# FPGA2.net
KiCad netlist of a schematic drawn in Altium Designer
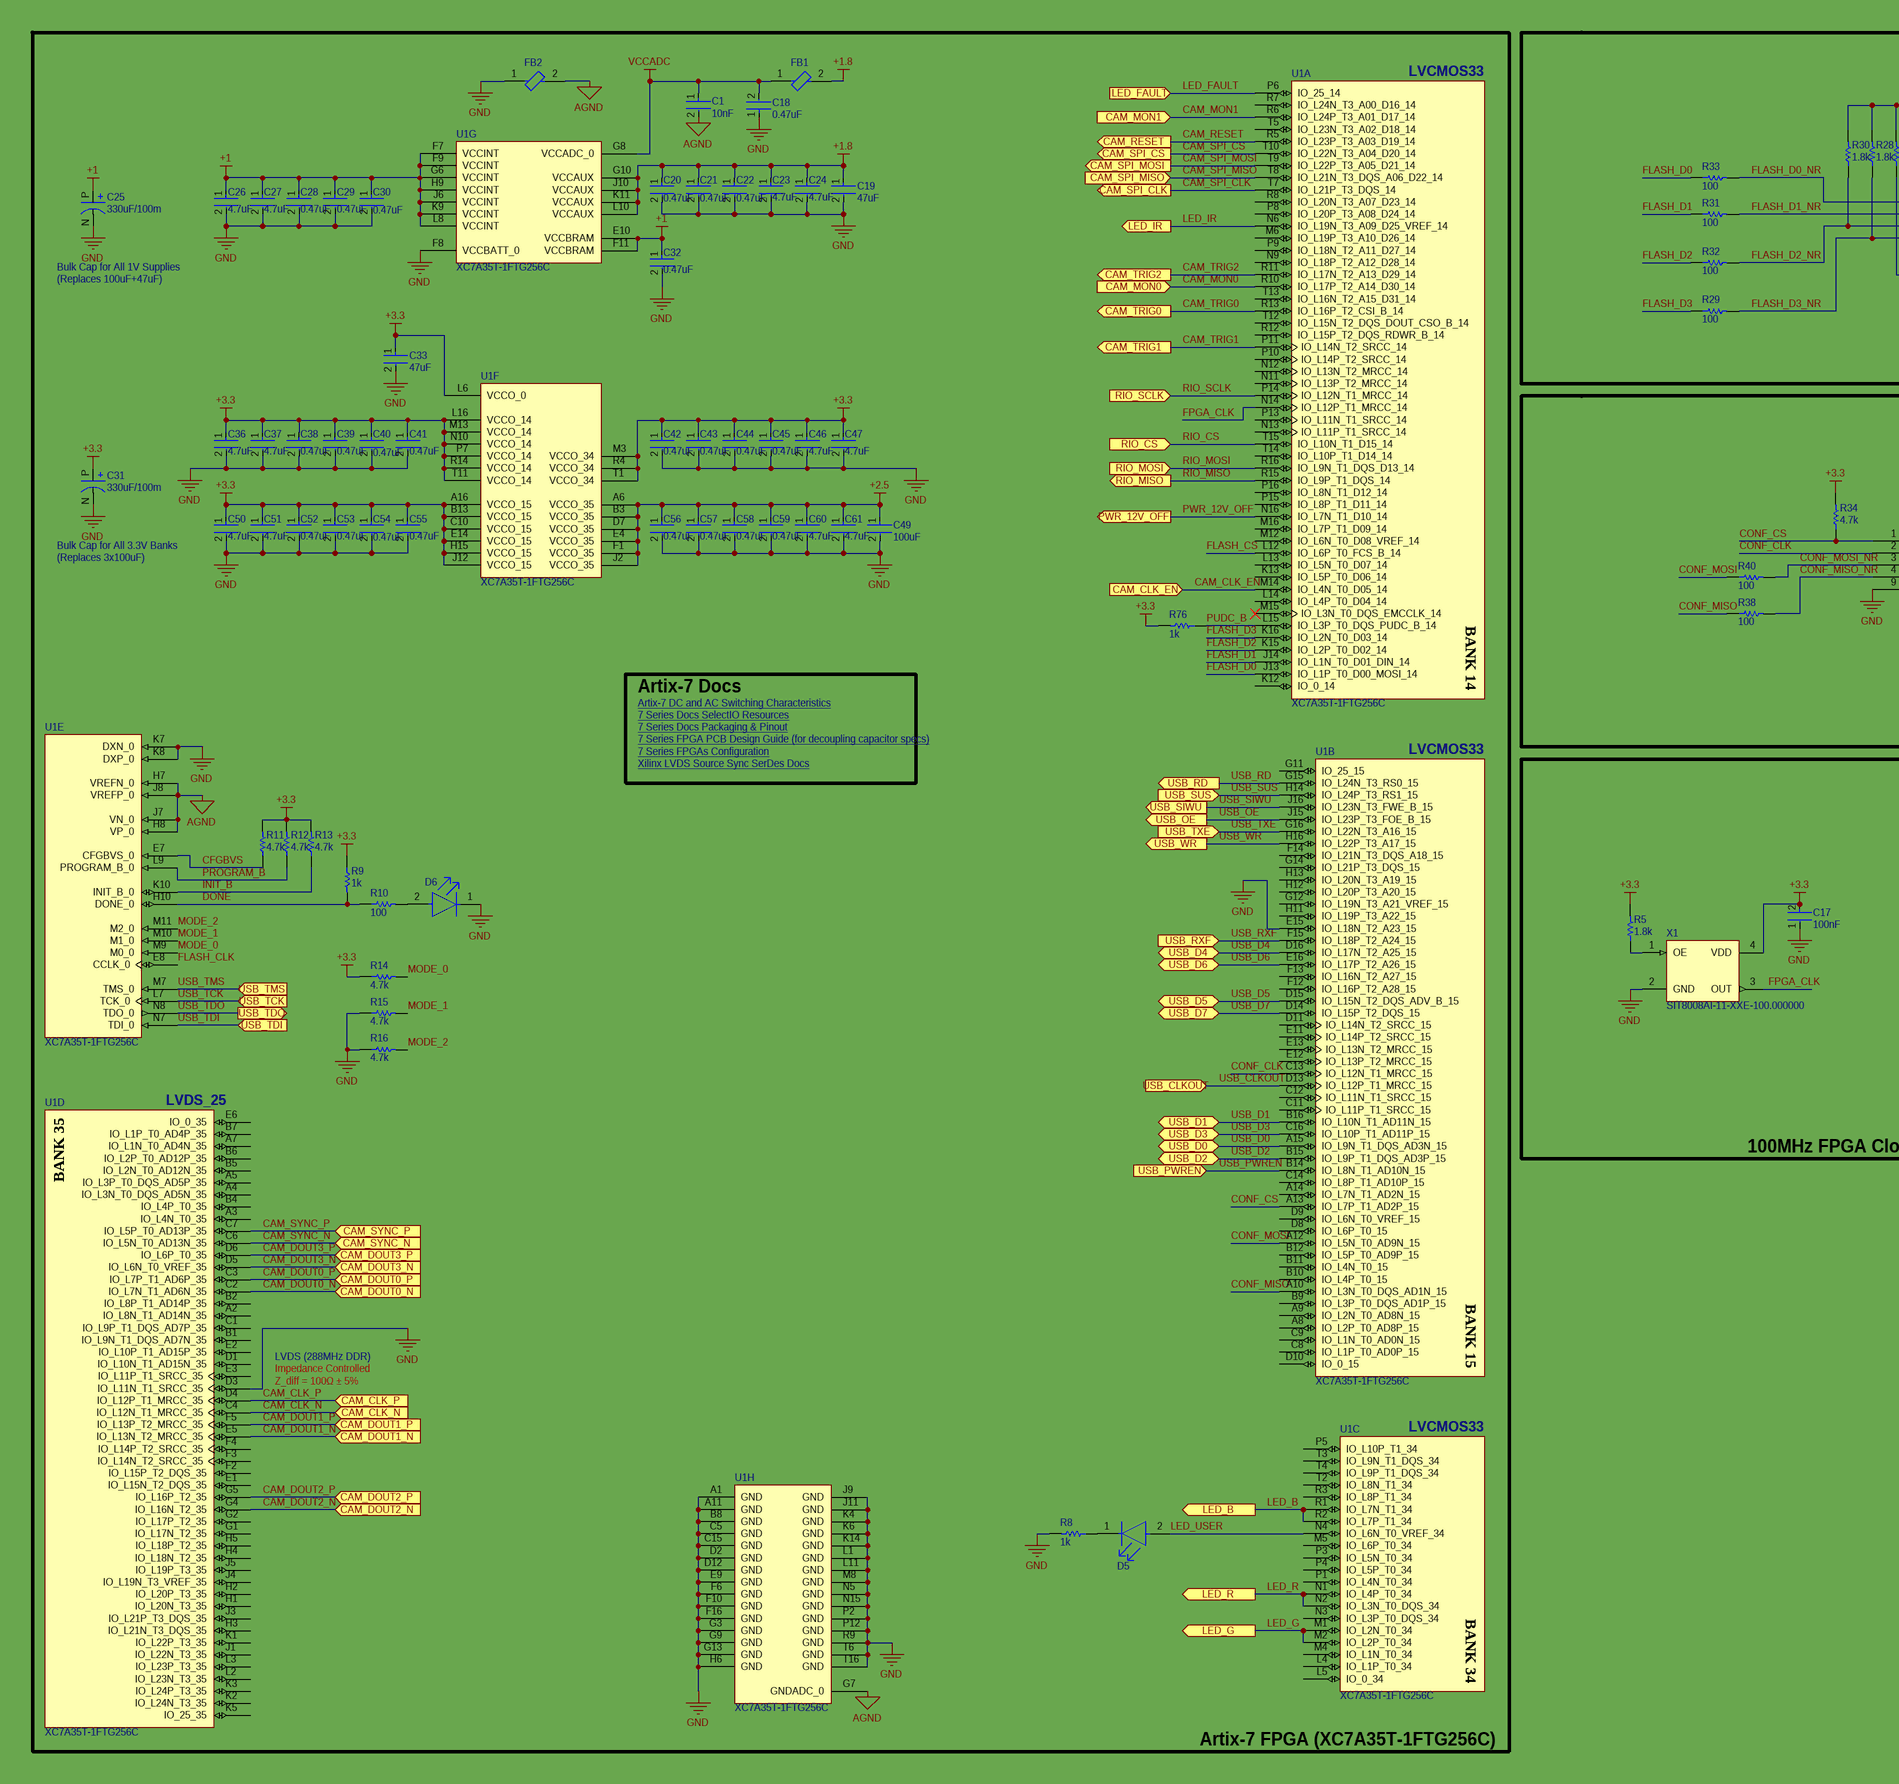
[diagram p0: FPGA2.SchDoc, left]
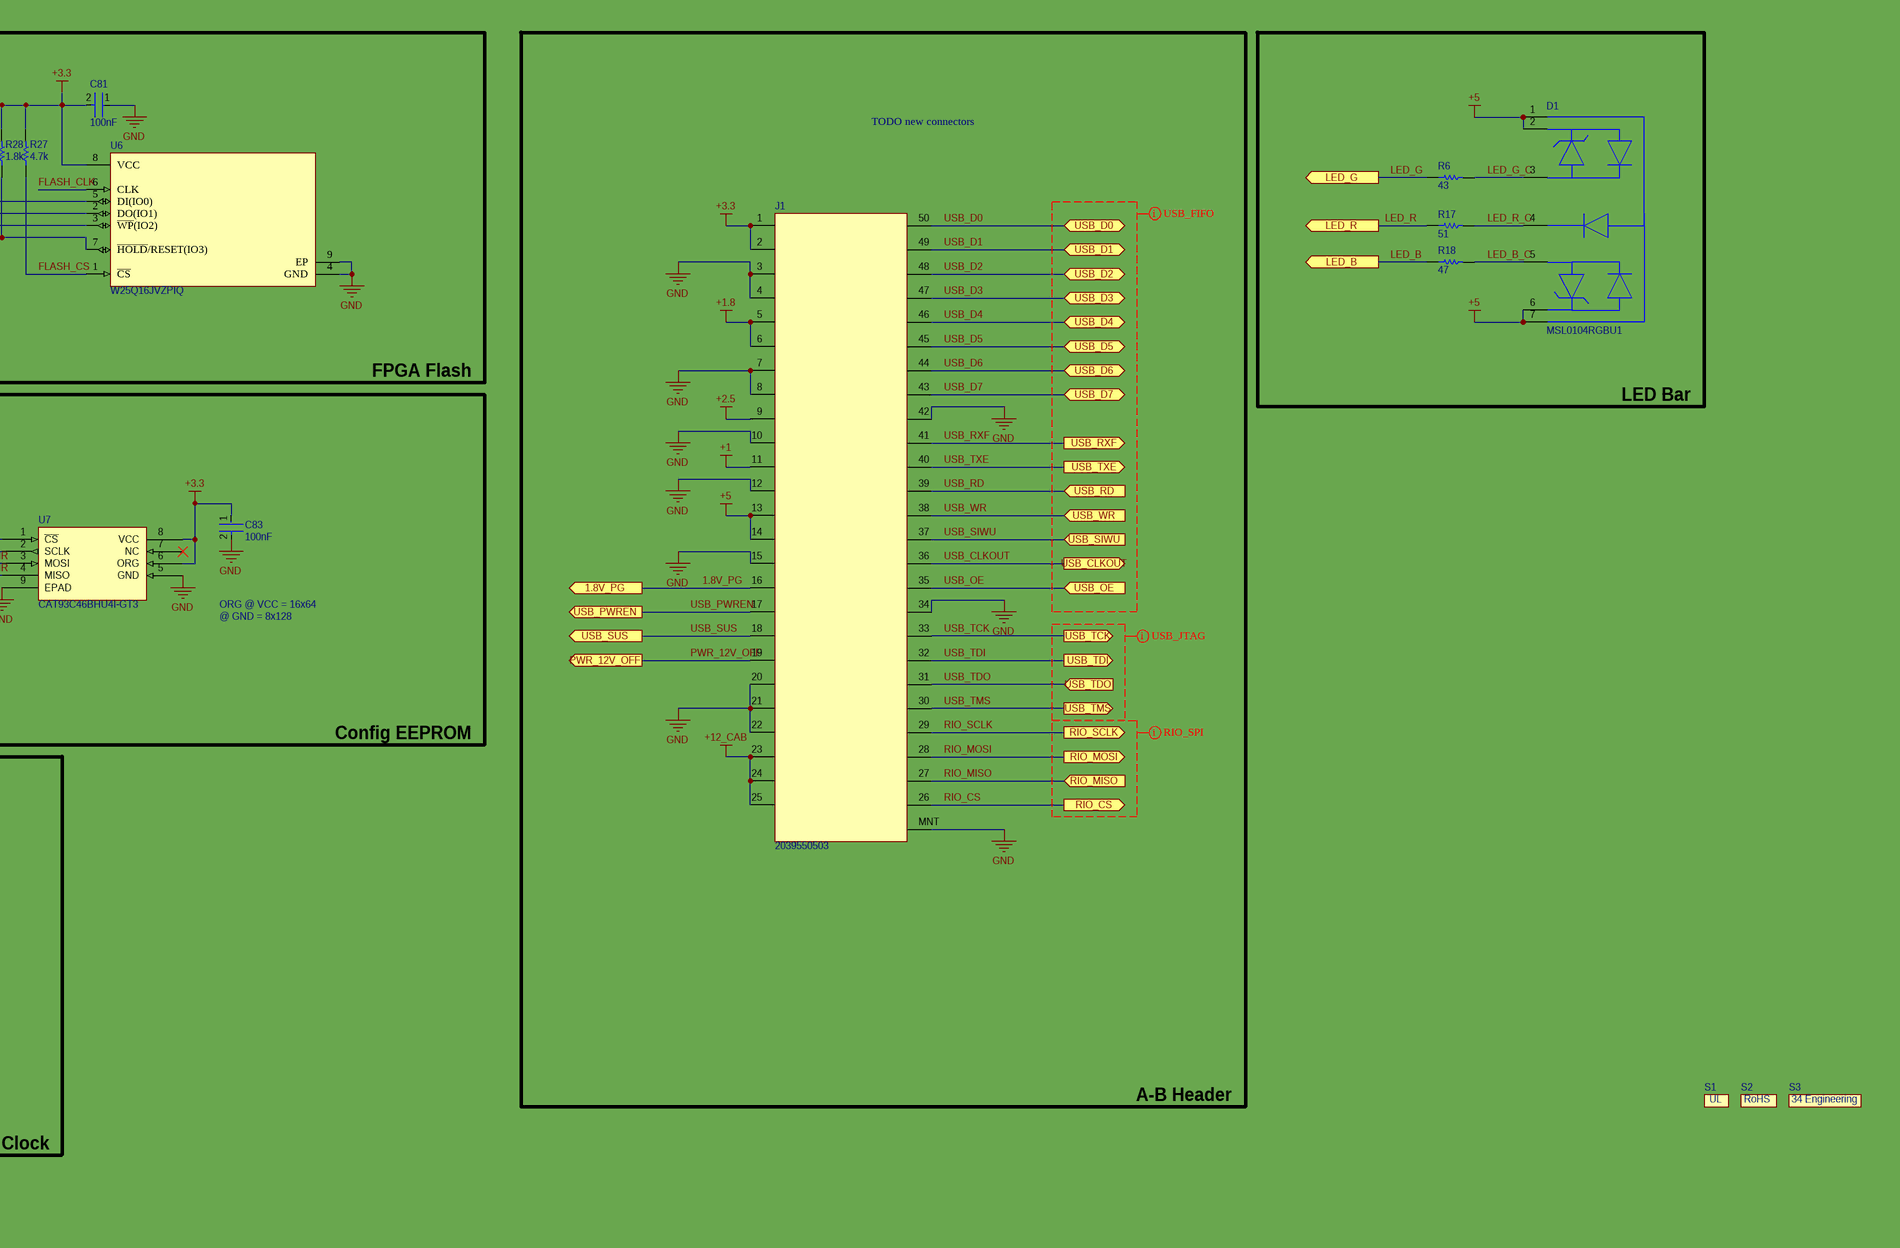
[diagram p1: FPGA2.SchDoc, right]

(export (version "E")
  (design (tool "Eeschema 10.0.6"))
  (components
    (comp (ref "C1")
      (value "10nF")
      (footprint "FP-GRM033-0_03-IPC_C")
      (description "Chip Multilayer Ceramic Capacitors for General Purpose, 0201, 10000pF, X7R, 15%, 10%, 10V")
      (fields (field (name "VOLTAGE") "10V") (field (name "TOLERANCE") "10%"))
      (libsource (lib "Altium Content Vault") (part "b4654b650e69147ec39a6b967a45e02"))
    )
    (comp (ref "C17")
      (value "100nF")
      (footprint "FP-GRM15-IPC_C")
      (description "CAP CER 0.1UF 16V X7R 0402")
      (fields (field (name "MANUFACTURER PART NUMBER") "GRM155R71C104KA88D") (field (name "TOLERANCE") "10%"))
      (libsource (lib "Altium Content Vault") (part "236180d848d6139a670b325ea6854c9"))
    )
    (comp (ref "C18")
      (value "0.47uF")
      (footprint "FP-GRM033-0_03-IPC_C")
      (description "Chip Multilayer Ceramic Capacitors for General Purpose, 0201, 0.47uF, X5R, 15%, 10%, 6.3V")
      (fields (field (name "TOLERANCE") "10%"))
      (libsource (lib "Altium Content Vault") (part "b4654b650e69147ec39a6b967a45e02"))
    )
    (comp (ref "C19")
      (value "47uF")
      (footprint "FP-GRM188-0_2-MFG")
      (description "Chip Multilayer Ceramic Capacitors for General Purpose, 0603, 47uF, X5R, 15%, 20%, 6.3V")
      (fields (field (name "TOLERANCE") "20%"))
      (libsource (lib "Altium Content Vault") (part "11868f565c42a9108669ba33697ecf6"))
    )
    (comp (ref "C20")
      (value "0.47uF")
      (footprint "FP-GRM033-0_03-IPC_C")
      (description "Chip Multilayer Ceramic Capacitors for General Purpose, 0201, 0.47uF, X5R, 15%, 10%, 6.3V")
      (fields (field (name "TOLERANCE") "10%"))
      (libsource (lib "Altium Content Vault") (part "b4654b650e69147ec39a6b967a45e02"))
    )
    (comp (ref "C21")
      (value "0.47uF")
      (footprint "FP-GRM033-0_03-IPC_C")
      (description "Chip Multilayer Ceramic Capacitors for General Purpose, 0201, 0.47uF, X5R, 15%, 10%, 6.3V")
      (fields (field (name "TOLERANCE") "10%"))
      (libsource (lib "Altium Content Vault") (part "b4654b650e69147ec39a6b967a45e02"))
    )
    (comp (ref "C22")
      (value "0.47uF")
      (footprint "FP-GRM033-0_03-IPC_C")
      (description "Chip Multilayer Ceramic Capacitors for General Purpose, 0201, 0.47uF, X5R, 15%, 10%, 6.3V")
      (fields (field (name "TOLERANCE") "10%"))
      (libsource (lib "Altium Content Vault") (part "b4654b650e69147ec39a6b967a45e02"))
    )
    (comp (ref "C23")
      (value "4.7uF")
      (footprint "FP-GRM155-0_1-IPC_B")
      (description "Chip Multilayer Ceramic Capacitors for General Purpose, 0402, 4.7uF, X5R, 15%, 20%, 6.3V")
      (fields (field (name "VOLTAGE") "6.3V") (field (name "TOLERANCE") "20%"))
      (libsource (lib "Altium Content Vault") (part "11868f565c42a9108669ba33697ecf6"))
    )
    (comp (ref "C24")
      (value "4.7uF")
      (footprint "FP-GRM155-0_1-IPC_B")
      (description "Chip Multilayer Ceramic Capacitors for General Purpose, 0402, 4.7uF, X5R, 15%, 20%, 6.3V")
      (fields (field (name "VOLTAGE") "6.3V") (field (name "TOLERANCE") "20%"))
      (libsource (lib "Altium Content Vault") (part "11868f565c42a9108669ba33697ecf6"))
    )
    (comp (ref "C25")
      (value "330uF/100m")
      (footprint "NOSD337M004R0100")
      (description "330uF +/-20% 4 V dc SMD Niobium Capacitor; 7343-31 package; ESR 0.1Ohms NOS")
      (fields
        (field (name "MANUFACTURER") "Kyocera AVX")
        (field (name "MANUFACTURER PART NUMBER") "NOSD337M004R0100")
      )
      (libsource (lib "Virtex") (part "NOSD337M004R0100"))
    )
    (comp (ref "C26")
      (value "4.7uF")
      (footprint "FP-GRM155-0_1-IPC_B")
      (description "Chip Multilayer Ceramic Capacitors for General Purpose, 0402, 4.7uF, X5R, 15%, 20%, 6.3V")
      (fields (field (name "VOLTAGE") "6.3V") (field (name "TOLERANCE") "20%"))
      (libsource (lib "Altium Content Vault") (part "11868f565c42a9108669ba33697ecf6"))
    )
    (comp (ref "C27")
      (value "4.7uF")
      (footprint "FP-GRM155-0_1-IPC_B")
      (description "Chip Multilayer Ceramic Capacitors for General Purpose, 0402, 4.7uF, X5R, 15%, 20%, 6.3V")
      (fields (field (name "VOLTAGE") "6.3V") (field (name "TOLERANCE") "20%"))
      (libsource (lib "Altium Content Vault") (part "11868f565c42a9108669ba33697ecf6"))
    )
    (comp (ref "C28")
      (value "0.47uF")
      (footprint "FP-GRM033-0_03-IPC_C")
      (description "Chip Multilayer Ceramic Capacitors for General Purpose, 0201, 0.47uF, X5R, 15%, 10%, 6.3V")
      (fields (field (name "TOLERANCE") "10%"))
      (libsource (lib "Altium Content Vault") (part "b4654b650e69147ec39a6b967a45e02"))
    )
    (comp (ref "C29")
      (value "0.47uF")
      (footprint "FP-GRM033-0_03-IPC_C")
      (description "Chip Multilayer Ceramic Capacitors for General Purpose, 0201, 0.47uF, X5R, 15%, 10%, 6.3V")
      (fields (field (name "TOLERANCE") "10%"))
      (libsource (lib "Altium Content Vault") (part "b4654b650e69147ec39a6b967a45e02"))
    )
    (comp (ref "C30")
      (value "0.47uF")
      (footprint "FP-GRM033-0_03-IPC_C")
      (description "Chip Multilayer Ceramic Capacitors for General Purpose, 0201, 0.47uF, X5R, 15%, 10%, 6.3V")
      (fields (field (name "TOLERANCE") "10%"))
      (libsource (lib "Altium Content Vault") (part "b4654b650e69147ec39a6b967a45e02"))
    )
    (comp (ref "C31")
      (value "330uF/100m")
      (footprint "NOSD337M004R0100")
      (description "330uF +/-20% 4 V dc SMD Niobium Capacitor; 7343-31 package; ESR 0.1Ohms NOS")
      (fields
        (field (name "MANUFACTURER") "Kyocera AVX")
        (field (name "MANUFACTURER PART NUMBER") "NOSD337M004R0100")
      )
      (libsource (lib "Virtex") (part "NOSD337M004R0100"))
    )
    (comp (ref "C32")
      (value "0.47uF")
      (footprint "FP-GRM033-0_03-IPC_C")
      (description "Chip Multilayer Ceramic Capacitors for General Purpose, 0201, 0.47uF, X5R, 15%, 10%, 6.3V")
      (fields (field (name "TOLERANCE") "10%"))
      (libsource (lib "Altium Content Vault") (part "b4654b650e69147ec39a6b967a45e02"))
    )
    (comp (ref "C33")
      (value "47uF")
      (footprint "FP-GRM188-0_2-MFG")
      (description "Chip Multilayer Ceramic Capacitors for General Purpose, 0603, 47uF, X5R, 15%, 20%, 6.3V")
      (fields (field (name "TOLERANCE") "20%"))
      (libsource (lib "Altium Content Vault") (part "11868f565c42a9108669ba33697ecf6"))
    )
    (comp (ref "C36")
      (value "4.7uF")
      (footprint "FP-GRM155-0_1-IPC_B")
      (description "Chip Multilayer Ceramic Capacitors for General Purpose, 0402, 4.7uF, X5R, 15%, 20%, 6.3V")
      (fields (field (name "VOLTAGE") "6.3V") (field (name "TOLERANCE") "20%"))
      (libsource (lib "Altium Content Vault") (part "11868f565c42a9108669ba33697ecf6"))
    )
    (comp (ref "C37")
      (value "4.7uF")
      (footprint "FP-GRM155-0_1-IPC_B")
      (description "Chip Multilayer Ceramic Capacitors for General Purpose, 0402, 4.7uF, X5R, 15%, 20%, 6.3V")
      (fields (field (name "VOLTAGE") "6.3V") (field (name "TOLERANCE") "20%"))
      (libsource (lib "Altium Content Vault") (part "11868f565c42a9108669ba33697ecf6"))
    )
    (comp (ref "C38")
      (value "0.47uF")
      (footprint "FP-GRM033-0_03-IPC_C")
      (description "Chip Multilayer Ceramic Capacitors for General Purpose, 0201, 0.47uF, X5R, 15%, 10%, 6.3V")
      (fields (field (name "TOLERANCE") "10%"))
      (libsource (lib "Altium Content Vault") (part "b4654b650e69147ec39a6b967a45e02"))
    )
    (comp (ref "C39")
      (value "0.47uF")
      (footprint "FP-GRM033-0_03-IPC_C")
      (description "Chip Multilayer Ceramic Capacitors for General Purpose, 0201, 0.47uF, X5R, 15%, 10%, 6.3V")
      (fields (field (name "TOLERANCE") "10%"))
      (libsource (lib "Altium Content Vault") (part "b4654b650e69147ec39a6b967a45e02"))
    )
    (comp (ref "C40")
      (value "0.47uF")
      (footprint "FP-GRM033-0_03-IPC_C")
      (description "Chip Multilayer Ceramic Capacitors for General Purpose, 0201, 0.47uF, X5R, 15%, 10%, 6.3V")
      (fields (field (name "TOLERANCE") "10%"))
      (libsource (lib "Altium Content Vault") (part "b4654b650e69147ec39a6b967a45e02"))
    )
    (comp (ref "C41")
      (value "0.47uF")
      (footprint "FP-GRM033-0_03-IPC_C")
      (description "Chip Multilayer Ceramic Capacitors for General Purpose, 0201, 0.47uF, X5R, 15%, 10%, 6.3V")
      (fields (field (name "TOLERANCE") "10%"))
      (libsource (lib "Altium Content Vault") (part "b4654b650e69147ec39a6b967a45e02"))
    )
    (comp (ref "C42")
      (value "0.47uF")
      (footprint "FP-GRM033-0_03-IPC_C")
      (description "Chip Multilayer Ceramic Capacitors for General Purpose, 0201, 0.47uF, X5R, 15%, 10%, 6.3V")
      (fields (field (name "TOLERANCE") "10%"))
      (libsource (lib "Altium Content Vault") (part "b4654b650e69147ec39a6b967a45e02"))
    )
    (comp (ref "C43")
      (value "0.47uF")
      (footprint "FP-GRM033-0_03-IPC_C")
      (description "Chip Multilayer Ceramic Capacitors for General Purpose, 0201, 0.47uF, X5R, 15%, 10%, 6.3V")
      (fields (field (name "TOLERANCE") "10%"))
      (libsource (lib "Altium Content Vault") (part "b4654b650e69147ec39a6b967a45e02"))
    )
    (comp (ref "C44")
      (value "0.47uF")
      (footprint "FP-GRM033-0_03-IPC_C")
      (description "Chip Multilayer Ceramic Capacitors for General Purpose, 0201, 0.47uF, X5R, 15%, 10%, 6.3V")
      (fields (field (name "TOLERANCE") "10%"))
      (libsource (lib "Altium Content Vault") (part "b4654b650e69147ec39a6b967a45e02"))
    )
    (comp (ref "C45")
      (value "0.47uF")
      (footprint "FP-GRM033-0_03-IPC_C")
      (description "Chip Multilayer Ceramic Capacitors for General Purpose, 0201, 0.47uF, X5R, 15%, 10%, 6.3V")
      (fields (field (name "TOLERANCE") "10%"))
      (libsource (lib "Altium Content Vault") (part "b4654b650e69147ec39a6b967a45e02"))
    )
    (comp (ref "C46")
      (value "4.7uF")
      (footprint "FP-GRM155-0_1-IPC_B")
      (description "Chip Multilayer Ceramic Capacitors for General Purpose, 0402, 4.7uF, X5R, 15%, 20%, 6.3V")
      (fields (field (name "VOLTAGE") "6.3V") (field (name "TOLERANCE") "20%"))
      (libsource (lib "Altium Content Vault") (part "11868f565c42a9108669ba33697ecf6"))
    )
    (comp (ref "C47")
      (value "4.7uF")
      (footprint "FP-GRM155-0_1-IPC_B")
      (description "Chip Multilayer Ceramic Capacitors for General Purpose, 0402, 4.7uF, X5R, 15%, 20%, 6.3V")
      (fields (field (name "VOLTAGE") "6.3V") (field (name "TOLERANCE") "20%"))
      (libsource (lib "Altium Content Vault") (part "11868f565c42a9108669ba33697ecf6"))
    )
    (comp (ref "C49")
      (value "100uF")
      (footprint "FP-GRM21B-0_2-e0_2_0_7-MFG")
      (description "Chip Multilayer Ceramic Capacitors for General Purpose, 0805, 100uF, X5R, 15%, 20%, 6.3V")
      (fields (field (name "TOLERANCE") "20%"))
      (libsource (lib "Altium Content Vault") (part "b4654b650e69147ec39a6b967a45e02"))
    )
    (comp (ref "C50")
      (value "4.7uF")
      (footprint "FP-GRM155-0_1-IPC_B")
      (description "Chip Multilayer Ceramic Capacitors for General Purpose, 0402, 4.7uF, X5R, 15%, 20%, 6.3V")
      (fields (field (name "VOLTAGE") "6.3V") (field (name "TOLERANCE") "20%"))
      (libsource (lib "Altium Content Vault") (part "11868f565c42a9108669ba33697ecf6"))
    )
    (comp (ref "C51")
      (value "4.7uF")
      (footprint "FP-GRM155-0_1-IPC_B")
      (description "Chip Multilayer Ceramic Capacitors for General Purpose, 0402, 4.7uF, X5R, 15%, 20%, 6.3V")
      (fields (field (name "VOLTAGE") "6.3V") (field (name "TOLERANCE") "20%"))
      (libsource (lib "Altium Content Vault") (part "11868f565c42a9108669ba33697ecf6"))
    )
    (comp (ref "C52")
      (value "0.47uF")
      (footprint "FP-GRM033-0_03-IPC_C")
      (description "Chip Multilayer Ceramic Capacitors for General Purpose, 0201, 0.47uF, X5R, 15%, 10%, 6.3V")
      (fields (field (name "TOLERANCE") "10%"))
      (libsource (lib "Altium Content Vault") (part "b4654b650e69147ec39a6b967a45e02"))
    )
    (comp (ref "C53")
      (value "0.47uF")
      (footprint "FP-GRM033-0_03-IPC_C")
      (description "Chip Multilayer Ceramic Capacitors for General Purpose, 0201, 0.47uF, X5R, 15%, 10%, 6.3V")
      (fields (field (name "TOLERANCE") "10%"))
      (libsource (lib "Altium Content Vault") (part "b4654b650e69147ec39a6b967a45e02"))
    )
    (comp (ref "C54")
      (value "0.47uF")
      (footprint "FP-GRM033-0_03-IPC_C")
      (description "Chip Multilayer Ceramic Capacitors for General Purpose, 0201, 0.47uF, X5R, 15%, 10%, 6.3V")
      (fields (field (name "TOLERANCE") "10%"))
      (libsource (lib "Altium Content Vault") (part "b4654b650e69147ec39a6b967a45e02"))
    )
    (comp (ref "C55")
      (value "0.47uF")
      (footprint "FP-GRM033-0_03-IPC_C")
      (description "Chip Multilayer Ceramic Capacitors for General Purpose, 0201, 0.47uF, X5R, 15%, 10%, 6.3V")
      (fields (field (name "TOLERANCE") "10%"))
      (libsource (lib "Altium Content Vault") (part "b4654b650e69147ec39a6b967a45e02"))
    )
    (comp (ref "C56")
      (value "0.47uF")
      (footprint "FP-GRM033-0_03-IPC_C")
      (description "Chip Multilayer Ceramic Capacitors for General Purpose, 0201, 0.47uF, X5R, 15%, 10%, 6.3V")
      (fields (field (name "TOLERANCE") "10%"))
      (libsource (lib "Altium Content Vault") (part "b4654b650e69147ec39a6b967a45e02"))
    )
    (comp (ref "C57")
      (value "0.47uF")
      (footprint "FP-GRM033-0_03-IPC_C")
      (description "Chip Multilayer Ceramic Capacitors for General Purpose, 0201, 0.47uF, X5R, 15%, 10%, 6.3V")
      (fields (field (name "TOLERANCE") "10%"))
      (libsource (lib "Altium Content Vault") (part "b4654b650e69147ec39a6b967a45e02"))
    )
    (comp (ref "C58")
      (value "0.47uF")
      (footprint "FP-GRM033-0_03-IPC_C")
      (description "Chip Multilayer Ceramic Capacitors for General Purpose, 0201, 0.47uF, X5R, 15%, 10%, 6.3V")
      (fields (field (name "TOLERANCE") "10%"))
      (libsource (lib "Altium Content Vault") (part "b4654b650e69147ec39a6b967a45e02"))
    )
    (comp (ref "C59")
      (value "0.47uF")
      (footprint "FP-GRM033-0_03-IPC_C")
      (description "Chip Multilayer Ceramic Capacitors for General Purpose, 0201, 0.47uF, X5R, 15%, 10%, 6.3V")
      (fields (field (name "TOLERANCE") "10%"))
      (libsource (lib "Altium Content Vault") (part "b4654b650e69147ec39a6b967a45e02"))
    )
    (comp (ref "C60")
      (value "4.7uF")
      (footprint "FP-GRM155-0_1-IPC_B")
      (description "Chip Multilayer Ceramic Capacitors for General Purpose, 0402, 4.7uF, X5R, 15%, 20%, 6.3V")
      (fields (field (name "VOLTAGE") "6.3V") (field (name "TOLERANCE") "20%"))
      (libsource (lib "Altium Content Vault") (part "11868f565c42a9108669ba33697ecf6"))
    )
    (comp (ref "C61")
      (value "4.7uF")
      (footprint "FP-GRM155-0_1-IPC_B")
      (description "Chip Multilayer Ceramic Capacitors for General Purpose, 0402, 4.7uF, X5R, 15%, 20%, 6.3V")
      (fields (field (name "VOLTAGE") "6.3V") (field (name "TOLERANCE") "20%"))
      (libsource (lib "Altium Content Vault") (part "11868f565c42a9108669ba33697ecf6"))
    )
    (comp (ref "C81")
      (value "100nF")
      (footprint "FP-GRM15-MFG")
      (description "CAP CER 0.1UF 16V X7R 0402")
      (fields (field (name "MANUFACTURER PART NUMBER") "GRM155R71C104KA88D") (field (name "TOLERANCE") "10%"))
      (libsource (lib "Altium Content Vault") (part "236180d848d6139a670b325ea6854c9"))
    )
    (comp (ref "C83")
      (value "100nF")
      (footprint "FP-GRM15-MFG")
      (description "CAP CER 0.1UF 16V X7R 0402")
      (fields (field (name "MANUFACTURER PART NUMBER") "GRM155R71C104KA88D") (field (name "TOLERANCE") "10%"))
      (libsource (lib "Altium Content Vault") (part "236180d848d6139a670b325ea6854c9"))
    )
    (comp (ref "D1")
      (value "MSL0104RGBU1")
      (footprint "FP-MSL0104-MFG")
      (description "LED RGB DIFFUSED 2709 SMD R/A")
      (fields
        (field (name "OCTOPART") "https://octopart.com/msl0104rgbu1-rohm-71139759")
        (field (name "MANUFACTURER") "Rohm")
      )
      (libsource (lib "Altium Content Vault") (part "c1ae77389a615bb85b9424d60117df8"))
    )
    (comp (ref "D5")
      (value "SML-D12U1WT86")
      (footprint "FP-SML-D12-MFG")
      (description "LED RED DIFFUSED 1608 SMD")
      (fields
        (field (name "MANUFACTURER") "Rohm")
        (field (name "OCTOPART") "https://octopart.com/sml-d12u1wt86-rohm-70850259")
      )
      (libsource (lib "Altium Content Vault") (part "8706943c75ba83719d021d2fdc84c58"))
    )
    (comp (ref "D6")
      (value "SML-D12U1WT86")
      (footprint "FP-SML-D12-MFG")
      (description "LED RED DIFFUSED 1608 SMD")
      (fields
        (field (name "MANUFACTURER") "Rohm")
        (field (name "OCTOPART") "https://octopart.com/sml-d12u1wt86-rohm-70850259")
      )
      (libsource (lib "Altium Content Vault") (part "8706943c75ba83719d021d2fdc84c58"))
    )
    (comp (ref "FB1")
      (value "BLM18AG601SN1D")
      (footprint "FP-BLM18-0_15-t0_8-MFG")
      (description "Chip Ferrite Bead, 0603, 600Ω @ 100MHz, 0.38Ω, 25%, 500mA")
      (fields (field (name "TOLERANCE") "25%"))
      (libsource (lib "Altium Content Vault") (part "5f30dd21d616792df468990f7003faa"))
    )
    (comp (ref "FB2")
      (value "BLM18AG601SN1D")
      (footprint "FP-BLM18-0_15-t0_8-MFG")
      (description "Chip Ferrite Bead, 0603, 600Ω @ 100MHz, 0.38Ω, 25%, 500mA")
      (fields (field (name "TOLERANCE") "25%"))
      (libsource (lib "Altium Content Vault") (part "5f30dd21d616792df468990f7003faa"))
    )
    (comp (ref "J1")
      (value "2039550503")
      (footprint "2039550503")
      (fields (field (name "MANUFACTURER") "Molex") (field (name "MANUFACTURER PART NUMBER") "203955-0503"))
      (libsource (lib "Virtex") (part "2039550503"))
    )
    (comp (ref "R5")
      (value "1.8k")
      (footprint "RESC1005X40X25LL05T05")
      (fields (field (name "MANUFACTURER") "Panasonic") (field (name "PART NUMBER") "ERJ2RKF1801X"))
      (libsource (lib "Altium Content Vault") (part "RES"))
    )
    (comp (ref "R6")
      (value "43")
      (footprint "RESC0603X26X15ML03T05")
      (fields (field (name "MANUFACTURER") "Panasonic") (field (name "PART NUMBER") "ERJ1GNF43R0C"))
      (libsource (lib "Altium Content Vault") (part "RES"))
    )
    (comp (ref "R8")
      (value "1k")
      (footprint "RESC1005X40X25NL05T05")
      (description "Chip Resistor, 1 KOhm, +/- 1%, 100 mW, -55 to 155 degC, 0402 (1005 Metric), RoHS, Tape and Reel")
      (fields (field (name "PARTNUMBER") "ERJ-2RKF1001X") (field (name "MANUFACTURER") "Basic Passives"))
      (libsource (lib "Altium Content Vault") (part "RES-2"))
    )
    (comp (ref "R9")
      (value "1k")
      (footprint "RESC1005X40X25NL05T05")
      (description "Chip Resistor, 1 KOhm, +/- 1%, 100 mW, -55 to 155 degC, 0402 (1005 Metric), RoHS, Tape and Reel")
      (fields (field (name "PARTNUMBER") "ERJ-2RKF1001X") (field (name "MANUFACTURER") "Basic Passives"))
      (libsource (lib "Altium Content Vault") (part "RES-2"))
    )
    (comp (ref "R10")
      (value "100")
      (footprint "RESC1005X40X25LL05T05")
      (description "Chip Resistor, 100 Ohm, +/- 1%, 100 mW, -55 to 155 degC, 0402 (1005 Metric), RoHS, Tape and Reel")
      (fields (field (name "MANUFACTURER") "Basic Passives") (field (name "TOLERANCE") "1%"))
      (libsource (lib "Altium Content Vault") (part "RES-2"))
    )
    (comp (ref "R11")
      (value "4.7k")
      (footprint "RESC1005X40X25LL05T05")
      (description "Chip Resistor, 4.7 KOhm, +/- 1%, 0.1 W, -55 to 155 degC, 0402 (1005 Metric), RoHS, Tape and Reel")
      (fields (field (name "TOLERANCE") "1%") (field (name "PARTNUMBER") "ERJ-2RKF4701X"))
      (libsource (lib "Altium Content Vault") (part "RES-2"))
    )
    (comp (ref "R12")
      (value "4.7k")
      (footprint "RESC1005X40X25LL05T05")
      (description "Chip Resistor, 4.7 KOhm, +/- 1%, 0.1 W, -55 to 155 degC, 0402 (1005 Metric), RoHS, Tape and Reel")
      (fields (field (name "TOLERANCE") "1%") (field (name "PARTNUMBER") "ERJ-2RKF4701X"))
      (libsource (lib "Altium Content Vault") (part "RES-2"))
    )
    (comp (ref "R13")
      (value "4.7k")
      (footprint "RESC1005X40X25LL05T05")
      (description "Chip Resistor, 4.7 KOhm, +/- 1%, 0.1 W, -55 to 155 degC, 0402 (1005 Metric), RoHS, Tape and Reel")
      (fields (field (name "TOLERANCE") "1%") (field (name "PARTNUMBER") "ERJ-2RKF4701X"))
      (libsource (lib "Altium Content Vault") (part "RES-2"))
    )
    (comp (ref "R14")
      (value "4.7k")
      (footprint "RESC1005X40X25LL05T05")
      (description "Chip Resistor, 4.7 KOhm, +/- 1%, 0.1 W, -55 to 155 degC, 0402 (1005 Metric), RoHS, Tape and Reel")
      (fields (field (name "TOLERANCE") "1%") (field (name "PARTNUMBER") "ERJ-2RKF4701X"))
      (libsource (lib "Altium Content Vault") (part "RES-2"))
    )
    (comp (ref "R15")
      (value "4.7k")
      (footprint "RESC1005X40X25LL05T05")
      (description "Chip Resistor, 4.7 KOhm, +/- 1%, 0.1 W, -55 to 155 degC, 0402 (1005 Metric), RoHS, Tape and Reel")
      (fields (field (name "TOLERANCE") "1%") (field (name "PARTNUMBER") "ERJ-2RKF4701X"))
      (libsource (lib "Altium Content Vault") (part "RES-2"))
    )
    (comp (ref "R16")
      (value "4.7k")
      (footprint "RESC1005X40X25LL05T05")
      (description "Chip Resistor, 4.7 KOhm, +/- 1%, 0.1 W, -55 to 155 degC, 0402 (1005 Metric), RoHS, Tape and Reel")
      (fields (field (name "TOLERANCE") "1%") (field (name "PARTNUMBER") "ERJ-2RKF4701X"))
      (libsource (lib "Altium Content Vault") (part "RES-2"))
    )
    (comp (ref "R17")
      (value "51")
      (footprint "RESC1608X55X30NL15T15")
      (fields (field (name "PART NUMBER") "ERJ3EKF51R0V") (field (name "MANUFACTURER") "Panasonic"))
      (libsource (lib "Altium Content Vault") (part "RES"))
    )
    (comp (ref "R18")
      (value "47")
      (footprint "RESC1608X55X30NL15T15")
      (description "Chip Resistor, 47 Ohm, +/- 1%, 0.1 W, -55 to 155 degC, 0603 (1608 Metric), RoHS, Tape and Reel")
      (fields (field (name "TOLERANCE") "1%"))
      (libsource (lib "Altium Content Vault") (part "RES-2"))
    )
    (comp (ref "R27")
      (value "4.7k")
      (footprint "RESC1005X40X25NL05T05")
      (description "Chip Resistor, 4.7 KOhm, +/- 1%, 0.1 W, -55 to 155 degC, 0402 (1005 Metric), RoHS, Tape and Reel")
      (fields (field (name "TOLERANCE") "1%") (field (name "PARTNUMBER") "ERJ-2RKF4701X"))
      (libsource (lib "Altium Content Vault") (part "RES-2"))
    )
    (comp (ref "R28")
      (value "1.8k")
      (footprint "RESC1005X40X25LL05T05")
      (fields (field (name "MANUFACTURER") "Panasonic") (field (name "PART NUMBER") "ERJ2RKF1801X"))
      (libsource (lib "Altium Content Vault") (part "RES"))
    )
    (comp (ref "R29")
      (value "100")
      (footprint "RESC1005X40X25LL05T05")
      (description "Chip Resistor, 100 Ohm, +/- 1%, 100 mW, -55 to 155 degC, 0402 (1005 Metric), RoHS, Tape and Reel")
      (fields (field (name "MANUFACTURER") "Basic Passives") (field (name "TOLERANCE") "1%"))
      (libsource (lib "Altium Content Vault") (part "RES-2"))
    )
    (comp (ref "R30")
      (value "1.8k")
      (footprint "RESC1005X40X25LL05T05")
      (fields (field (name "MANUFACTURER") "Panasonic") (field (name "PART NUMBER") "ERJ2RKF1801X"))
      (libsource (lib "Altium Content Vault") (part "RES"))
    )
    (comp (ref "R31")
      (value "100")
      (footprint "RESC1005X40X25LL05T05")
      (description "Chip Resistor, 100 Ohm, +/- 1%, 100 mW, -55 to 155 degC, 0402 (1005 Metric), RoHS, Tape and Reel")
      (fields (field (name "MANUFACTURER") "Basic Passives") (field (name "TOLERANCE") "1%"))
      (libsource (lib "Altium Content Vault") (part "RES-2"))
    )
    (comp (ref "R32")
      (value "100")
      (footprint "RESC1005X40X25LL05T05")
      (description "Chip Resistor, 100 Ohm, +/- 1%, 100 mW, -55 to 155 degC, 0402 (1005 Metric), RoHS, Tape and Reel")
      (fields (field (name "MANUFACTURER") "Basic Passives") (field (name "TOLERANCE") "1%"))
      (libsource (lib "Altium Content Vault") (part "RES-2"))
    )
    (comp (ref "R33")
      (value "100")
      (footprint "RESC1005X40X25LL05T05")
      (description "Chip Resistor, 100 Ohm, +/- 1%, 100 mW, -55 to 155 degC, 0402 (1005 Metric), RoHS, Tape and Reel")
      (fields (field (name "MANUFACTURER") "Basic Passives") (field (name "TOLERANCE") "1%"))
      (libsource (lib "Altium Content Vault") (part "RES-2"))
    )
    (comp (ref "R34")
      (value "4.7k")
      (footprint "RESC1005X40X25NL05T05")
      (description "Chip Resistor, 4.7 KOhm, +/- 1%, 0.1 W, -55 to 155 degC, 0402 (1005 Metric), RoHS, Tape and Reel")
      (fields (field (name "TOLERANCE") "1%") (field (name "PARTNUMBER") "ERJ-2RKF4701X"))
      (libsource (lib "Altium Content Vault") (part "RES-2"))
    )
    (comp (ref "R38")
      (value "100")
      (footprint "RESC1005X40X25LL05T05")
      (description "Chip Resistor, 100 Ohm, +/- 1%, 100 mW, -55 to 155 degC, 0402 (1005 Metric), RoHS, Tape and Reel")
      (fields (field (name "MANUFACTURER") "Basic Passives") (field (name "TOLERANCE") "1%"))
      (libsource (lib "Altium Content Vault") (part "RES-2"))
    )
    (comp (ref "R40")
      (value "100")
      (footprint "RESC1005X40X25LL05T05")
      (description "Chip Resistor, 100 Ohm, +/- 1%, 100 mW, -55 to 155 degC, 0402 (1005 Metric), RoHS, Tape and Reel")
      (fields (field (name "MANUFACTURER") "Basic Passives") (field (name "TOLERANCE") "1%"))
      (libsource (lib "Altium Content Vault") (part "RES-2"))
    )
    (comp (ref "R76")
      (value "1k")
      (footprint "RESC0603X26X15LL03T05")
      (fields (field (name "MANUFACTURER") "Panasonic") (field (name "PART NUMBER") "ERJ1GNF1001C"))
      (libsource (lib "Altium Content Vault") (part "RES"))
    )
    (comp (ref "S1") (value "~") (footprint "UL") (libsource (lib "Virtex") (part "UL")))
    (comp (ref "S2") (value "~") (footprint "RoHS") (libsource (lib "Virtex") (part "RoHS")))
    (comp (ref "S3")
      (value "~")
      (footprint "34EngineeringLogo")
      (description "34 Engineering Silkscreen Logo")
      (libsource (lib "Virtex") (part "34EngineeringLogo"))
    )
    (comp (ref "U1")
      (value "XC7A35T-1FTG256C")
      (footprint "FTG256")
      (description "Artix-7 FPGA, 170 User I/Os, 0 GTP, 256-Ball BGA, Speed Grade 1, Commercial Grade, Pb-Free")
      (fields (field (name "MANUFACTURER") "Xilinx"))
      (libsource (lib "Altium Content Vault") (part "XLNX-XC7A35T-FTG256"))
    )
    (comp (ref "U6")
      (value "W25Q16JVZPIQ")
      (footprint "FP-ZP-IPC_B")
      (description "IC FLASH 16MBIT SPI/QUAD 8WSON")
      (libsource (lib "Altium Content Vault") (part "4cb77c13ae9adfb05a25f85e82aeb43"))
    )
    (comp (ref "U7")
      (value "CAT93C46BHU4I-GT3")
      (footprint "CAT93C46BHU4I-GT3")
      (description "EEPROM Memory IC 1Kb (128 x 8, 64 x 16) SPI 4 MHz 8-UDFN-EP (2x3)")
      (libsource (lib "Virtex") (part "CAT93C46BHU4I-GT3"))
    )
    (comp (ref "X1")
      (value "SIT8008AI-11-XXE-100.000000")
      (footprint "SIT8008AI-11-XXE-100.000000")
      (fields
        (field (name "MANUFACTURER") "SiTime")
        (field (name "MANUFACTURER PART NUMBER") "SIT8008AI-11-XXE-100.000000E")
      )
      (libsource (lib "Virtex") (part "SIT8008AI-11-XXE-100.000000"))
    )
  )
  (nets
    (net (code "1") (name "+1") (class "Default")
      (node (ref "C25") (pin "P") (pintype "passive"))
      (node (ref "C26") (pin "1") (pinfunction "1_1") (pintype "passive"))
      (node (ref "C27") (pin "1") (pinfunction "1_1") (pintype "passive"))
      (node (ref "C28") (pin "1") (pinfunction "1_1") (pintype "passive"))
      (node (ref "C29") (pin "1") (pinfunction "1_1") (pintype "passive"))
      (node (ref "C30") (pin "1") (pinfunction "1_1") (pintype "passive"))
      (node (ref "C32") (pin "1") (pinfunction "1_1") (pintype "passive"))
      (node (ref "J1") (pin "11") (pintype "passive"))
      (node (ref "U1") (pin "E10") (pinfunction "VCCBRAM_E10") (pintype "power_in"))
      (node (ref "U1") (pin "F11") (pinfunction "VCCBRAM_F11") (pintype "power_in"))
      (node (ref "U1") (pin "F7") (pinfunction "VCCINT_F7") (pintype "power_in"))
      (node (ref "U1") (pin "F9") (pinfunction "VCCINT_F9") (pintype "power_in"))
      (node (ref "U1") (pin "G6") (pinfunction "VCCINT_G6") (pintype "power_in"))
      (node (ref "U1") (pin "H9") (pinfunction "VCCINT_H9") (pintype "power_in"))
      (node (ref "U1") (pin "J6") (pinfunction "VCCINT_J6") (pintype "power_in"))
      (node (ref "U1") (pin "K9") (pinfunction "VCCINT_K9") (pintype "power_in"))
      (node (ref "U1") (pin "L8") (pinfunction "VCCINT_L8") (pintype "power_in"))
    )
    (net (code "2") (name "+1.8") (class "Default")
      (node (ref "C19") (pin "1") (pinfunction "1_1") (pintype "passive"))
      (node (ref "C20") (pin "1") (pinfunction "1_1") (pintype "passive"))
      (node (ref "C21") (pin "1") (pinfunction "1_1") (pintype "passive"))
      (node (ref "C22") (pin "1") (pinfunction "1_1") (pintype "passive"))
      (node (ref "C23") (pin "1") (pinfunction "1_1") (pintype "passive"))
      (node (ref "C24") (pin "1") (pinfunction "1_1") (pintype "passive"))
      (node (ref "FB1") (pin "2") (pinfunction "2_2") (pintype "passive"))
      (node (ref "J1") (pin "5") (pintype "passive"))
      (node (ref "J1") (pin "6") (pintype "passive"))
      (node (ref "U1") (pin "G10") (pinfunction "VCCAUX_G10") (pintype "power_in"))
      (node (ref "U1") (pin "J10") (pinfunction "VCCAUX_J10") (pintype "power_in"))
      (node (ref "U1") (pin "K11") (pinfunction "VCCAUX_K11") (pintype "power_in"))
      (node (ref "U1") (pin "L10") (pinfunction "VCCAUX_L10") (pintype "power_in"))
    )
    (net (code "3") (name "+2.5") (class "Default")
      (node (ref "C49") (pin "1") (pinfunction "1_1") (pintype "passive"))
      (node (ref "C56") (pin "1") (pinfunction "1_1") (pintype "passive"))
      (node (ref "C57") (pin "1") (pinfunction "1_1") (pintype "passive"))
      (node (ref "C58") (pin "1") (pinfunction "1_1") (pintype "passive"))
      (node (ref "C59") (pin "1") (pinfunction "1_1") (pintype "passive"))
      (node (ref "C60") (pin "1") (pinfunction "1_1") (pintype "passive"))
      (node (ref "C61") (pin "1") (pinfunction "1_1") (pintype "passive"))
      (node (ref "J1") (pin "9") (pintype "passive"))
      (node (ref "U1") (pin "A6") (pinfunction "VCCO_35_A6") (pintype "power_in"))
      (node (ref "U1") (pin "B3") (pinfunction "VCCO_35_B3") (pintype "power_in"))
      (node (ref "U1") (pin "D7") (pinfunction "VCCO_35_D7") (pintype "power_in"))
      (node (ref "U1") (pin "E4") (pinfunction "VCCO_35_E4") (pintype "power_in"))
      (node (ref "U1") (pin "F1") (pinfunction "VCCO_35_F1") (pintype "power_in"))
      (node (ref "U1") (pin "J2") (pinfunction "VCCO_35_J2") (pintype "power_in"))
    )
    (net (code "4") (name "+3.3") (class "Default")
      (node (ref "C17") (pin "2") (pinfunction "2_2") (pintype "passive"))
      (node (ref "C31") (pin "P") (pintype "passive"))
      (node (ref "C33") (pin "1") (pinfunction "1_1") (pintype "passive"))
      (node (ref "C36") (pin "1") (pinfunction "1_1") (pintype "passive"))
      (node (ref "C37") (pin "1") (pinfunction "1_1") (pintype "passive"))
      (node (ref "C38") (pin "1") (pinfunction "1_1") (pintype "passive"))
      (node (ref "C39") (pin "1") (pinfunction "1_1") (pintype "passive"))
      (node (ref "C40") (pin "1") (pinfunction "1_1") (pintype "passive"))
      (node (ref "C41") (pin "1") (pinfunction "1_1") (pintype "passive"))
      (node (ref "C42") (pin "1") (pinfunction "1_1") (pintype "passive"))
      (node (ref "C43") (pin "1") (pinfunction "1_1") (pintype "passive"))
      (node (ref "C44") (pin "1") (pinfunction "1_1") (pintype "passive"))
      (node (ref "C45") (pin "1") (pinfunction "1_1") (pintype "passive"))
      (node (ref "C46") (pin "1") (pinfunction "1_1") (pintype "passive"))
      (node (ref "C47") (pin "1") (pinfunction "1_1") (pintype "passive"))
      (node (ref "C50") (pin "1") (pinfunction "1_1") (pintype "passive"))
      (node (ref "C51") (pin "1") (pinfunction "1_1") (pintype "passive"))
      (node (ref "C52") (pin "1") (pinfunction "1_1") (pintype "passive"))
      (node (ref "C53") (pin "1") (pinfunction "1_1") (pintype "passive"))
      (node (ref "C54") (pin "1") (pinfunction "1_1") (pintype "passive"))
      (node (ref "C55") (pin "1") (pinfunction "1_1") (pintype "passive"))
      (node (ref "C81") (pin "2") (pinfunction "2_2") (pintype "passive"))
      (node (ref "C83") (pin "1") (pinfunction "1_1") (pintype "passive"))
      (node (ref "J1") (pin "1") (pintype "passive"))
      (node (ref "J1") (pin "2") (pintype "passive"))
      (node (ref "R11") (pin "2") (pinfunction "2_2") (pintype "passive"))
      (node (ref "R12") (pin "2") (pinfunction "2_2") (pintype "passive"))
      (node (ref "R13") (pin "2") (pinfunction "2_2") (pintype "passive"))
      (node (ref "R14") (pin "1") (pinfunction "1_1") (pintype "passive"))
      (node (ref "R27") (pin "2") (pinfunction "2_2") (pintype "passive"))
      (node (ref "R28") (pin "2") (pinfunction "2_2") (pintype "passive"))
      (node (ref "R30") (pin "2") (pinfunction "2_2") (pintype "passive"))
      (node (ref "R34") (pin "2") (pinfunction "2_2") (pintype "passive"))
      (node (ref "R5") (pin "2") (pinfunction "2_2") (pintype "passive"))
      (node (ref "R76") (pin "2") (pinfunction "2_2") (pintype "passive"))
      (node (ref "R9") (pin "1") (pinfunction "1_1") (pintype "passive"))
      (node (ref "U1") (pin "A16") (pinfunction "VCCO_15_A16") (pintype "power_in"))
      (node (ref "U1") (pin "B13") (pinfunction "VCCO_15_B13") (pintype "power_in"))
      (node (ref "U1") (pin "C10") (pinfunction "VCCO_15_C10") (pintype "power_in"))
      (node (ref "U1") (pin "E14") (pinfunction "VCCO_15_E14") (pintype "power_in"))
      (node (ref "U1") (pin "H15") (pinfunction "VCCO_15_H15") (pintype "power_in"))
      (node (ref "U1") (pin "J12") (pinfunction "VCCO_15_J12") (pintype "power_in"))
      (node (ref "U1") (pin "L16") (pinfunction "VCCO_14_L16") (pintype "power_in"))
      (node (ref "U1") (pin "L6") (pinfunction "VCCO_0_L6") (pintype "power_in"))
      (node (ref "U1") (pin "M13") (pinfunction "VCCO_14_M13") (pintype "power_in"))
      (node (ref "U1") (pin "M3") (pinfunction "VCCO_34_M3") (pintype "power_in"))
      (node (ref "U1") (pin "N10") (pinfunction "VCCO_14_N10") (pintype "power_in"))
      (node (ref "U1") (pin "P7") (pinfunction "VCCO_14_P7") (pintype "power_in"))
      (node (ref "U1") (pin "R14") (pinfunction "VCCO_14_R14") (pintype "power_in"))
      (node (ref "U1") (pin "R4") (pinfunction "VCCO_34_R4") (pintype "power_in"))
      (node (ref "U1") (pin "T1") (pinfunction "VCCO_34_T1") (pintype "power_in"))
      (node (ref "U1") (pin "T11") (pinfunction "VCCO_14_T11") (pintype "power_in"))
      (node (ref "U6") (pin "8") (pinfunction "VCC_8") (pintype "power_in"))
      (node (ref "U7") (pin "6") (pinfunction "ORG_6") (pintype "input"))
      (node (ref "U7") (pin "8") (pinfunction "VCC_8") (pintype "power_in"))
      (node (ref "X1") (pin "4") (pinfunction "VDD_4") (pintype "power_in"))
    )
    (net (code "5") (name "+5") (class "Default")
      (node (ref "D1") (pin "1") (pinfunction "R_A_1") (pintype "passive"))
      (node (ref "D1") (pin "2") (pinfunction "G_A_2") (pintype "passive"))
      (node (ref "D1") (pin "6") (pinfunction "B_A_6") (pintype "passive"))
      (node (ref "D1") (pin "7") (pinfunction "R_A_7") (pintype "passive"))
      (node (ref "J1") (pin "13") (pintype "passive"))
      (node (ref "J1") (pin "14") (pintype "passive"))
    )
    (net (code "6") (name "+12_CAB") (class "Default")
      (node (ref "J1") (pin "23") (pintype "passive"))
      (node (ref "J1") (pin "24") (pintype "passive"))
      (node (ref "J1") (pin "25") (pintype "passive"))
    )
    (net (code "7") (name "/1.8V_PG") (class "Default") (node (ref "J1") (pin "16") (pintype "passive")))
    (net (code "8") (name "/CAM_CLK_EN") (class "Default")
      (node (ref "U1") (pin "M14") (pinfunction "IO_L4N_T0_D05_14_M14") (pintype "bidirectional"))
    )
    (net (code "9") (name "/CAM_CLK_N") (class "Default")
      (node (ref "U1") (pin "C4") (pinfunction "IO_L12N_T1_MRCC_35_C4") (pintype "bidirectional"))
    )
    (net (code "10") (name "/CAM_CLK_P") (class "Default")
      (node (ref "U1") (pin "D4") (pinfunction "IO_L12P_T1_MRCC_35_D4") (pintype "bidirectional"))
    )
    (net (code "11") (name "/CAM_DOUT0_N") (class "Default")
      (node (ref "U1") (pin "C2") (pinfunction "IO_L7N_T1_AD6N_35_C2") (pintype "bidirectional"))
    )
    (net (code "12") (name "/CAM_DOUT0_P") (class "Default")
      (node (ref "U1") (pin "C3") (pinfunction "IO_L7P_T1_AD6P_35_C3") (pintype "bidirectional"))
    )
    (net (code "13") (name "/CAM_DOUT1_N") (class "Default")
      (node (ref "U1") (pin "E5") (pinfunction "IO_L13N_T2_MRCC_35_E5") (pintype "bidirectional"))
    )
    (net (code "14") (name "/CAM_DOUT1_P") (class "Default")
      (node (ref "U1") (pin "F5") (pinfunction "IO_L13P_T2_MRCC_35_F5") (pintype "bidirectional"))
    )
    (net (code "15") (name "/CAM_DOUT2_N") (class "Default")
      (node (ref "U1") (pin "G4") (pinfunction "IO_L16N_T2_35_G4") (pintype "bidirectional"))
    )
    (net (code "16") (name "/CAM_DOUT2_P") (class "Default")
      (node (ref "U1") (pin "G5") (pinfunction "IO_L16P_T2_35_G5") (pintype "bidirectional"))
    )
    (net (code "17") (name "/CAM_DOUT3_N") (class "Default")
      (node (ref "U1") (pin "D5") (pinfunction "IO_L6N_T0_VREF_35_D5") (pintype "bidirectional"))
    )
    (net (code "18") (name "/CAM_DOUT3_P") (class "Default")
      (node (ref "U1") (pin "D6") (pinfunction "IO_L6P_T0_35_D6") (pintype "bidirectional"))
    )
    (net (code "19") (name "/CAM_MON0") (class "Default")
      (node (ref "U1") (pin "R10") (pinfunction "IO_L17P_T2_A14_D30_14_R10") (pintype "bidirectional"))
    )
    (net (code "20") (name "/CAM_MON1") (class "Default")
      (node (ref "U1") (pin "R6") (pinfunction "IO_L24P_T3_A01_D17_14_R6") (pintype "bidirectional"))
    )
    (net (code "21") (name "/CAM_RESET") (class "Default")
      (node (ref "U1") (pin "R5") (pinfunction "IO_L23P_T3_A03_D19_14_R5") (pintype "bidirectional"))
    )
    (net (code "22") (name "/CAM_SPI_CLK") (class "Default")
      (node (ref "U1") (pin "T7") (pinfunction "IO_L21P_T3_DQS_14_T7") (pintype "bidirectional"))
    )
    (net (code "23") (name "/CAM_SPI_CS") (class "Default")
      (node (ref "U1") (pin "T10") (pinfunction "IO_L22N_T3_A04_D20_14_T10") (pintype "bidirectional"))
    )
    (net (code "24") (name "/CAM_SPI_MISO") (class "Default")
      (node (ref "U1") (pin "T8") (pinfunction "IO_L21N_T3_DQS_A06_D22_14_T8") (pintype "bidirectional"))
    )
    (net (code "25") (name "/CAM_SPI_MOSI") (class "Default")
      (node (ref "U1") (pin "T9") (pinfunction "IO_L22P_T3_A05_D21_14_T9") (pintype "bidirectional"))
    )
    (net (code "26") (name "/CAM_SYNC_N") (class "Default")
      (node (ref "U1") (pin "C6") (pinfunction "IO_L5N_T0_AD13N_35_C6") (pintype "bidirectional"))
    )
    (net (code "27") (name "/CAM_SYNC_P") (class "Default")
      (node (ref "U1") (pin "C7") (pinfunction "IO_L5P_T0_AD13P_35_C7") (pintype "bidirectional"))
    )
    (net (code "28") (name "/CAM_TRIG0") (class "Default")
      (node (ref "U1") (pin "R13") (pinfunction "IO_L16P_T2_CSI_B_14_R13") (pintype "bidirectional"))
    )
    (net (code "29") (name "/CAM_TRIG1") (class "Default")
      (node (ref "U1") (pin "P11") (pinfunction "IO_L14N_T2_SRCC_14_P11") (pintype "bidirectional"))
    )
    (net (code "30") (name "/CAM_TRIG2") (class "Default")
      (node (ref "U1") (pin "R11") (pinfunction "IO_L17N_T2_A13_D29_14_R11") (pintype "bidirectional"))
    )
    (net (code "31") (name "/CFGBVS") (class "Default")
      (node (ref "R11") (pin "1") (pinfunction "1_1") (pintype "passive"))
      (node (ref "U1") (pin "E7") (pinfunction "CFGBVS_0_E7") (pintype "input"))
    )
    (net (code "32") (name "/CONF_CLK") (class "Default")
      (node (ref "U1") (pin "C13") (pinfunction "IO_L12N_T1_MRCC_15_C13") (pintype "bidirectional"))
      (node (ref "U7") (pin "2") (pinfunction "SCLK_2") (pintype "output"))
    )
    (net (code "33") (name "/CONF_CS") (class "Default")
      (node (ref "R34") (pin "1") (pinfunction "1_1") (pintype "passive"))
      (node (ref "U1") (pin "A13") (pinfunction "IO_L7P_T1_AD2P_15_A13") (pintype "bidirectional"))
      (node (ref "U7") (pin "1") (pinfunction "~{CS}_1") (pintype "input"))
    )
    (net (code "34") (name "/CONF_MISO") (class "Default")
      (node (ref "R38") (pin "1") (pinfunction "1_1") (pintype "passive"))
      (node (ref "U1") (pin "A10") (pinfunction "IO_L3N_T0_DQS_AD1N_15_A10") (pintype "bidirectional"))
    )
    (net (code "35") (name "/CONF_MISO_NR") (class "Default")
      (node (ref "R38") (pin "2") (pinfunction "2_2") (pintype "passive"))
      (node (ref "U7") (pin "4") (pinfunction "MISO_4") (pintype "power_in"))
    )
    (net (code "36") (name "/CONF_MOSI") (class "Default")
      (node (ref "R40") (pin "1") (pinfunction "1_1") (pintype "passive"))
      (node (ref "U1") (pin "A12") (pinfunction "IO_L5N_T0_AD9N_15_A12") (pintype "bidirectional"))
    )
    (net (code "37") (name "/CONF_MOSI_NR") (class "Default")
      (node (ref "R40") (pin "2") (pinfunction "2_2") (pintype "passive"))
      (node (ref "U7") (pin "3") (pinfunction "MOSI_3") (pintype "input"))
    )
    (net (code "38") (name "/DONE") (class "Default")
      (node (ref "R10") (pin "1") (pinfunction "1_1") (pintype "passive"))
      (node (ref "R9") (pin "2") (pinfunction "2_2") (pintype "passive"))
      (node (ref "U1") (pin "H10") (pinfunction "DONE_0_H10") (pintype "bidirectional"))
    )
    (net (code "39") (name "/FLASH_CLK") (class "Default")
      (node (ref "U1") (pin "E8") (pinfunction "CCLK_0_E8") (pintype "bidirectional"))
      (node (ref "U6") (pin "6") (pinfunction "CLK_6") (pintype "input"))
    )
    (net (code "40") (name "/FLASH_CS") (class "Default")
      (node (ref "R27") (pin "1") (pinfunction "1_1") (pintype "passive"))
      (node (ref "U1") (pin "L12") (pinfunction "IO_L6P_T0_FCS_B_14_L12") (pintype "bidirectional"))
      (node (ref "U6") (pin "1") (pinfunction "~{CS}_1") (pintype "input"))
    )
    (net (code "41") (name "/FLASH_D0") (class "Default")
      (node (ref "R33") (pin "1") (pinfunction "1_1") (pintype "passive"))
      (node (ref "U1") (pin "J13") (pinfunction "IO_L1P_T0_D00_MOSI_14_J13") (pintype "bidirectional"))
    )
    (net (code "42") (name "/FLASH_D0_NR") (class "Default")
      (node (ref "R33") (pin "2") (pinfunction "2_2") (pintype "passive"))
      (node (ref "U6") (pin "5") (pinfunction "DI(IO0)_5") (pintype "bidirectional"))
    )
    (net (code "43") (name "/FLASH_D1") (class "Default")
      (node (ref "R31") (pin "1") (pinfunction "1_1") (pintype "passive"))
      (node (ref "U1") (pin "J14") (pinfunction "IO_L1N_T0_D01_DIN_14_J14") (pintype "bidirectional"))
    )
    (net (code "44") (name "/FLASH_D1_NR") (class "Default")
      (node (ref "R31") (pin "2") (pinfunction "2_2") (pintype "passive"))
      (node (ref "U6") (pin "2") (pinfunction "DO(IO1)_2") (pintype "bidirectional"))
    )
    (net (code "45") (name "/FLASH_D2") (class "Default")
      (node (ref "R32") (pin "1") (pinfunction "1_1") (pintype "passive"))
      (node (ref "U1") (pin "K15") (pinfunction "IO_L2P_T0_D02_14_K15") (pintype "bidirectional"))
    )
    (net (code "46") (name "/FLASH_D2_NR") (class "Default")
      (node (ref "R30") (pin "1") (pinfunction "1_1") (pintype "passive"))
      (node (ref "R32") (pin "2") (pinfunction "2_2") (pintype "passive"))
      (node (ref "U6") (pin "3") (pinfunction "~{WP}(IO2)_3") (pintype "bidirectional"))
    )
    (net (code "47") (name "/FLASH_D3") (class "Default")
      (node (ref "R29") (pin "1") (pinfunction "1_1") (pintype "passive"))
      (node (ref "U1") (pin "K16") (pinfunction "IO_L2N_T0_D03_14_K16") (pintype "bidirectional"))
    )
    (net (code "48") (name "/FLASH_D3_NR") (class "Default")
      (node (ref "R28") (pin "1") (pinfunction "1_1") (pintype "passive"))
      (node (ref "R29") (pin "2") (pinfunction "2_2") (pintype "passive"))
      (node (ref "U6") (pin "7") (pinfunction "~{HOLD}/RESET(IO3)_7") (pintype "bidirectional"))
    )
    (net (code "49") (name "/FPGA_CLK") (class "Default")
      (node (ref "U1") (pin "N14") (pinfunction "IO_L12P_T1_MRCC_14_N14") (pintype "bidirectional"))
      (node (ref "X1") (pin "3") (pinfunction "OUT_3") (pintype "output"))
    )
    (net (code "50") (name "/INIT_B") (class "Default")
      (node (ref "R13") (pin "1") (pinfunction "1_1") (pintype "passive"))
      (node (ref "U1") (pin "K10") (pinfunction "INIT_B_0_K10") (pintype "bidirectional"))
    )
    (net (code "51") (name "/LED_B") (class "Default")
      (node (ref "R18") (pin "1") (pinfunction "1_1") (pintype "passive"))
      (node (ref "U1") (pin "R1") (pinfunction "IO_L7N_T1_34_R1") (pintype "bidirectional"))
      (node (ref "U1") (pin "R2") (pinfunction "IO_L7P_T1_34_R2") (pintype "bidirectional"))
    )
    (net (code "52") (name "/LED_B_C") (class "Default")
      (node (ref "D1") (pin "5") (pinfunction "B_K_5") (pintype "passive"))
      (node (ref "R18") (pin "2") (pinfunction "2_2") (pintype "passive"))
    )
    (net (code "53") (name "/LED_FAULT") (class "Default")
      (node (ref "U1") (pin "P6") (pinfunction "IO_25_14_P6") (pintype "bidirectional"))
    )
    (net (code "54") (name "/LED_G") (class "Default")
      (node (ref "R6") (pin "1") (pinfunction "1_1") (pintype "passive"))
      (node (ref "U1") (pin "M1") (pinfunction "IO_L2N_T0_34_M1") (pintype "bidirectional"))
      (node (ref "U1") (pin "M2") (pinfunction "IO_L2P_T0_34_M2") (pintype "bidirectional"))
    )
    (net (code "55") (name "/LED_G_C") (class "Default")
      (node (ref "D1") (pin "3") (pinfunction "G_K_3") (pintype "passive"))
      (node (ref "R6") (pin "2") (pinfunction "2_2") (pintype "passive"))
    )
    (net (code "56") (name "/LED_IR") (class "Default")
      (node (ref "U1") (pin "N6") (pinfunction "IO_L19N_T3_A09_D25_VREF_14_N6") (pintype "bidirectional"))
    )
    (net (code "57") (name "/LED_R") (class "Default")
      (node (ref "R17") (pin "1") (pinfunction "1_1") (pintype "passive"))
      (node (ref "U1") (pin "N1") (pinfunction "IO_L4P_T0_34_N1") (pintype "bidirectional"))
      (node (ref "U1") (pin "N2") (pinfunction "IO_L3N_T0_DQS_34_N2") (pintype "bidirectional"))
    )
    (net (code "58") (name "/LED_R_C") (class "Default")
      (node (ref "D1") (pin "4") (pinfunction "R_K_4") (pintype "passive"))
      (node (ref "R17") (pin "2") (pinfunction "2_2") (pintype "passive"))
    )
    (net (code "59") (name "/LED_USER") (class "Default")
      (node (ref "D5") (pin "2") (pinfunction "A_2") (pintype "passive"))
      (node (ref "U1") (pin "N4") (pinfunction "IO_L6N_T0_VREF_34_N4") (pintype "bidirectional"))
    )
    (net (code "60") (name "/MODE_0") (class "Default")
      (node (ref "R14") (pin "2") (pinfunction "2_2") (pintype "passive"))
      (node (ref "U1") (pin "M9") (pinfunction "M0_0_M9") (pintype "input"))
    )
    (net (code "61") (name "/MODE_1") (class "Default")
      (node (ref "R15") (pin "2") (pinfunction "2_2") (pintype "passive"))
      (node (ref "U1") (pin "M10") (pinfunction "M1_0_M10") (pintype "input"))
    )
    (net (code "62") (name "/MODE_2") (class "Default")
      (node (ref "R16") (pin "2") (pinfunction "2_2") (pintype "passive"))
      (node (ref "U1") (pin "M11") (pinfunction "M2_0_M11") (pintype "input"))
    )
    (net (code "63") (name "/PROGRAM_B") (class "Default")
      (node (ref "R12") (pin "1") (pinfunction "1_1") (pintype "passive"))
      (node (ref "U1") (pin "L9") (pinfunction "PROGRAM_B_0_L9") (pintype "input"))
    )
    (net (code "64") (name "/PUDC_B") (class "Default")
      (node (ref "R76") (pin "1") (pinfunction "1_1") (pintype "passive"))
      (node (ref "U1") (pin "L15") (pinfunction "IO_L3P_T0_DQS_PUDC_B_14_L15") (pintype "bidirectional"))
    )
    (net (code "65") (name "/PWR_12V_OFF") (class "Default")
      (node (ref "J1") (pin "19") (pintype "passive"))
      (node (ref "U1") (pin "N16") (pinfunction "IO_L7N_T1_D10_14_N16") (pintype "bidirectional"))
    )
    (net (code "66") (name "/RIO_CS") (class "Default")
      (node (ref "J1") (pin "26") (pintype "passive"))
      (node (ref "U1") (pin "T15") (pinfunction "IO_L10N_T1_D15_14_T15") (pintype "bidirectional"))
    )
    (net (code "67") (name "/RIO_MISO") (class "Default")
      (node (ref "J1") (pin "27") (pintype "passive"))
      (node (ref "U1") (pin "R15") (pinfunction "IO_L9P_T1_DQS_14_R15") (pintype "bidirectional"))
    )
    (net (code "68") (name "/RIO_MOSI") (class "Default")
      (node (ref "J1") (pin "28") (pintype "passive"))
      (node (ref "U1") (pin "R16") (pinfunction "IO_L9N_T1_DQS_D13_14_R16") (pintype "bidirectional"))
    )
    (net (code "69") (name "/RIO_SCLK") (class "Default")
      (node (ref "J1") (pin "29") (pintype "passive"))
      (node (ref "U1") (pin "P14") (pinfunction "IO_L12N_T1_MRCC_14_P14") (pintype "bidirectional"))
    )
    (net (code "70") (name "/USB_CLKOUT") (class "Default")
      (node (ref "J1") (pin "36") (pintype "passive"))
      (node (ref "U1") (pin "D13") (pinfunction "IO_L12P_T1_MRCC_15_D13") (pintype "bidirectional"))
    )
    (net (code "71") (name "/USB_D0") (class "Default")
      (node (ref "J1") (pin "50") (pintype "passive"))
      (node (ref "U1") (pin "A15") (pinfunction "IO_L9N_T1_DQS_AD3N_15_A15") (pintype "bidirectional"))
    )
    (net (code "72") (name "/USB_D1") (class "Default")
      (node (ref "J1") (pin "49") (pintype "passive"))
      (node (ref "U1") (pin "B16") (pinfunction "IO_L10N_T1_AD11N_15_B16") (pintype "bidirectional"))
    )
    (net (code "73") (name "/USB_D2") (class "Default")
      (node (ref "J1") (pin "48") (pintype "passive"))
      (node (ref "U1") (pin "B15") (pinfunction "IO_L9P_T1_DQS_AD3P_15_B15") (pintype "bidirectional"))
    )
    (net (code "74") (name "/USB_D3") (class "Default")
      (node (ref "J1") (pin "47") (pintype "passive"))
      (node (ref "U1") (pin "C16") (pinfunction "IO_L10P_T1_AD11P_15_C16") (pintype "bidirectional"))
    )
    (net (code "75") (name "/USB_D4") (class "Default")
      (node (ref "J1") (pin "46") (pintype "passive"))
      (node (ref "U1") (pin "D16") (pinfunction "IO_L17N_T2_A25_15_D16") (pintype "bidirectional"))
    )
    (net (code "76") (name "/USB_D5") (class "Default")
      (node (ref "J1") (pin "45") (pintype "passive"))
      (node (ref "U1") (pin "D15") (pinfunction "IO_L15N_T2_DQS_ADV_B_15_D15") (pintype "bidirectional"))
    )
    (net (code "77") (name "/USB_D6") (class "Default")
      (node (ref "J1") (pin "44") (pintype "passive"))
      (node (ref "U1") (pin "E16") (pinfunction "IO_L17P_T2_A26_15_E16") (pintype "bidirectional"))
    )
    (net (code "78") (name "/USB_D7") (class "Default")
      (node (ref "J1") (pin "43") (pintype "passive"))
      (node (ref "U1") (pin "D14") (pinfunction "IO_L15P_T2_DQS_15_D14") (pintype "bidirectional"))
    )
    (net (code "79") (name "/USB_OE") (class "Default")
      (node (ref "J1") (pin "35") (pintype "passive"))
      (node (ref "U1") (pin "J15") (pinfunction "IO_L23P_T3_FOE_B_15_J15") (pintype "bidirectional"))
    )
    (net (code "80") (name "/USB_PWREN") (class "Default")
      (node (ref "J1") (pin "17") (pintype "passive"))
      (node (ref "U1") (pin "B14") (pinfunction "IO_L8N_T1_AD10N_15_B14") (pintype "bidirectional"))
    )
    (net (code "81") (name "/USB_RD") (class "Default")
      (node (ref "J1") (pin "39") (pintype "passive"))
      (node (ref "U1") (pin "G15") (pinfunction "IO_L24N_T3_RS0_15_G15") (pintype "bidirectional"))
    )
    (net (code "82") (name "/USB_RXF") (class "Default")
      (node (ref "J1") (pin "41") (pintype "passive"))
      (node (ref "U1") (pin "F15") (pinfunction "IO_L18P_T2_A24_15_F15") (pintype "bidirectional"))
    )
    (net (code "83") (name "/USB_SIWU") (class "Default")
      (node (ref "J1") (pin "37") (pintype "passive"))
      (node (ref "U1") (pin "J16") (pinfunction "IO_L23N_T3_FWE_B_15_J16") (pintype "bidirectional"))
    )
    (net (code "84") (name "/USB_SUS") (class "Default")
      (node (ref "J1") (pin "18") (pintype "passive"))
      (node (ref "U1") (pin "H14") (pinfunction "IO_L24P_T3_RS1_15_H14") (pintype "bidirectional"))
    )
    (net (code "85") (name "/USB_TCK") (class "Default")
      (node (ref "J1") (pin "33") (pintype "passive"))
      (node (ref "U1") (pin "L7") (pinfunction "TCK_0_L7") (pintype "input"))
    )
    (net (code "86") (name "/USB_TDI") (class "Default")
      (node (ref "J1") (pin "32") (pintype "passive"))
      (node (ref "U1") (pin "N7") (pinfunction "TDI_0_N7") (pintype "input"))
    )
    (net (code "87") (name "/USB_TDO") (class "Default")
      (node (ref "J1") (pin "31") (pintype "passive"))
      (node (ref "U1") (pin "N8") (pinfunction "TDO_0_N8") (pintype "output"))
    )
    (net (code "88") (name "/USB_TMS") (class "Default")
      (node (ref "J1") (pin "30") (pintype "passive"))
      (node (ref "U1") (pin "M7") (pinfunction "TMS_0_M7") (pintype "input"))
    )
    (net (code "89") (name "/USB_TXE") (class "Default")
      (node (ref "J1") (pin "40") (pintype "passive"))
      (node (ref "U1") (pin "G16") (pinfunction "IO_L22N_T3_A16_15_G16") (pintype "bidirectional"))
    )
    (net (code "90") (name "/USB_WR") (class "Default")
      (node (ref "J1") (pin "38") (pintype "passive"))
      (node (ref "U1") (pin "H16") (pinfunction "IO_L22P_T3_A17_15_H16") (pintype "bidirectional"))
    )
    (net (code "91") (name "AGND") (class "Default")
      (node (ref "C1") (pin "2") (pinfunction "2_2") (pintype "passive"))
      (node (ref "FB2") (pin "2") (pinfunction "2_2") (pintype "passive"))
      (node (ref "U1") (pin "G7") (pinfunction "GNDADC_0_G7") (pintype "power_in"))
      (node (ref "U1") (pin "H7") (pinfunction "VREFN_0_H7") (pintype "input"))
      (node (ref "U1") (pin "H8") (pinfunction "VP_0_H8") (pintype "input"))
      (node (ref "U1") (pin "J7") (pinfunction "VN_0_J7") (pintype "input"))
      (node (ref "U1") (pin "J8") (pinfunction "VREFP_0_J8") (pintype "input"))
    )
    (net (code "92") (name "GND") (class "Default")
      (node (ref "C17") (pin "1") (pinfunction "1_1") (pintype "passive"))
      (node (ref "C18") (pin "1") (pinfunction "1_1") (pintype "passive"))
      (node (ref "C19") (pin "2") (pinfunction "2_2") (pintype "passive"))
      (node (ref "C20") (pin "2") (pinfunction "2_2") (pintype "passive"))
      (node (ref "C21") (pin "2") (pinfunction "2_2") (pintype "passive"))
      (node (ref "C22") (pin "2") (pinfunction "2_2") (pintype "passive"))
      (node (ref "C23") (pin "2") (pinfunction "2_2") (pintype "passive"))
      (node (ref "C24") (pin "2") (pinfunction "2_2") (pintype "passive"))
      (node (ref "C25") (pin "N") (pintype "passive"))
      (node (ref "C26") (pin "2") (pinfunction "2_2") (pintype "passive"))
      (node (ref "C27") (pin "2") (pinfunction "2_2") (pintype "passive"))
      (node (ref "C28") (pin "2") (pinfunction "2_2") (pintype "passive"))
      (node (ref "C29") (pin "2") (pinfunction "2_2") (pintype "passive"))
      (node (ref "C30") (pin "2") (pinfunction "2_2") (pintype "passive"))
      (node (ref "C31") (pin "N") (pintype "passive"))
      (node (ref "C32") (pin "2") (pinfunction "2_2") (pintype "passive"))
      (node (ref "C33") (pin "2") (pinfunction "2_2") (pintype "passive"))
      (node (ref "C36") (pin "2") (pinfunction "2_2") (pintype "passive"))
      (node (ref "C37") (pin "2") (pinfunction "2_2") (pintype "passive"))
      (node (ref "C38") (pin "2") (pinfunction "2_2") (pintype "passive"))
      (node (ref "C39") (pin "2") (pinfunction "2_2") (pintype "passive"))
      (node (ref "C40") (pin "2") (pinfunction "2_2") (pintype "passive"))
      (node (ref "C41") (pin "2") (pinfunction "2_2") (pintype "passive"))
      (node (ref "C42") (pin "2") (pinfunction "2_2") (pintype "passive"))
      (node (ref "C43") (pin "2") (pinfunction "2_2") (pintype "passive"))
      (node (ref "C44") (pin "2") (pinfunction "2_2") (pintype "passive"))
      (node (ref "C45") (pin "2") (pinfunction "2_2") (pintype "passive"))
      (node (ref "C46") (pin "2") (pinfunction "2_2") (pintype "passive"))
      (node (ref "C47") (pin "2") (pinfunction "2_2") (pintype "passive"))
      (node (ref "C49") (pin "2") (pinfunction "2_2") (pintype "passive"))
      (node (ref "C50") (pin "2") (pinfunction "2_2") (pintype "passive"))
      (node (ref "C51") (pin "2") (pinfunction "2_2") (pintype "passive"))
      (node (ref "C52") (pin "2") (pinfunction "2_2") (pintype "passive"))
      (node (ref "C53") (pin "2") (pinfunction "2_2") (pintype "passive"))
      (node (ref "C54") (pin "2") (pinfunction "2_2") (pintype "passive"))
      (node (ref "C55") (pin "2") (pinfunction "2_2") (pintype "passive"))
      (node (ref "C56") (pin "2") (pinfunction "2_2") (pintype "passive"))
      (node (ref "C57") (pin "2") (pinfunction "2_2") (pintype "passive"))
      (node (ref "C58") (pin "2") (pinfunction "2_2") (pintype "passive"))
      (node (ref "C59") (pin "2") (pinfunction "2_2") (pintype "passive"))
      (node (ref "C60") (pin "2") (pinfunction "2_2") (pintype "passive"))
      (node (ref "C61") (pin "2") (pinfunction "2_2") (pintype "passive"))
      (node (ref "C81") (pin "1") (pinfunction "1_1") (pintype "passive"))
      (node (ref "C83") (pin "2") (pinfunction "2_2") (pintype "passive"))
      (node (ref "D6") (pin "1") (pinfunction "C_1") (pintype "passive"))
      (node (ref "FB2") (pin "1") (pinfunction "1_1") (pintype "passive"))
      (node (ref "J1") (pin "10") (pintype "passive"))
      (node (ref "J1") (pin "12") (pintype "passive"))
      (node (ref "J1") (pin "15") (pintype "passive"))
      (node (ref "J1") (pin "20") (pintype "passive"))
      (node (ref "J1") (pin "21") (pintype "passive"))
      (node (ref "J1") (pin "22") (pintype "passive"))
      (node (ref "J1") (pin "3") (pintype "passive"))
      (node (ref "J1") (pin "34") (pintype "passive"))
      (node (ref "J1") (pin "4") (pintype "passive"))
      (node (ref "J1") (pin "42") (pintype "passive"))
      (node (ref "J1") (pin "7") (pintype "passive"))
      (node (ref "J1") (pin "8") (pintype "passive"))
      (node (ref "J1") (pin "MNT") (pintype "passive"))
      (node (ref "R15") (pin "1") (pinfunction "1_1") (pintype "passive"))
      (node (ref "R16") (pin "1") (pinfunction "1_1") (pintype "passive"))
      (node (ref "R8") (pin "2") (pinfunction "2_2") (pintype "passive"))
      (node (ref "U1") (pin "A1") (pinfunction "GND_A1") (pintype "power_in"))
      (node (ref "U1") (pin "A11") (pinfunction "GND_A11") (pintype "power_in"))
      (node (ref "U1") (pin "B8") (pinfunction "GND_B8") (pintype "power_in"))
      (node (ref "U1") (pin "C15") (pinfunction "GND_C15") (pintype "power_in"))
      (node (ref "U1") (pin "C5") (pinfunction "GND_C5") (pintype "power_in"))
      (node (ref "U1") (pin "D12") (pinfunction "GND_D12") (pintype "power_in"))
      (node (ref "U1") (pin "D2") (pinfunction "GND_D2") (pintype "power_in"))
      (node (ref "U1") (pin "D3") (pinfunction "IO_L11N_T1_SRCC_35_D3") (pintype "bidirectional"))
      (node (ref "U1") (pin "E15") (pinfunction "IO_L18N_T2_A23_15_E15") (pintype "bidirectional"))
      (node (ref "U1") (pin "E9") (pinfunction "GND_E9") (pintype "power_in"))
      (node (ref "U1") (pin "F10") (pinfunction "GND_F10") (pintype "power_in"))
      (node (ref "U1") (pin "F16") (pinfunction "GND_F16") (pintype "power_in"))
      (node (ref "U1") (pin "F6") (pinfunction "GND_F6") (pintype "power_in"))
      (node (ref "U1") (pin "F8") (pinfunction "VCCBATT_0_F8") (pintype "power_in"))
      (node (ref "U1") (pin "G13") (pinfunction "GND_G13") (pintype "power_in"))
      (node (ref "U1") (pin "G3") (pinfunction "GND_G3") (pintype "power_in"))
      (node (ref "U1") (pin "G9") (pinfunction "GND_G9") (pintype "power_in"))
      (node (ref "U1") (pin "H6") (pinfunction "GND_H6") (pintype "power_in"))
      (node (ref "U1") (pin "J11") (pinfunction "GND_J11") (pintype "power_in"))
      (node (ref "U1") (pin "J9") (pinfunction "GND_J9") (pintype "power_in"))
      (node (ref "U1") (pin "K14") (pinfunction "GND_K14") (pintype "power_in"))
      (node (ref "U1") (pin "K4") (pinfunction "GND_K4") (pintype "power_in"))
      (node (ref "U1") (pin "K6") (pinfunction "GND_K6") (pintype "power_in"))
      (node (ref "U1") (pin "K7") (pinfunction "DXN_0_K7") (pintype "input"))
      (node (ref "U1") (pin "K8") (pinfunction "DXP_0_K8") (pintype "input"))
      (node (ref "U1") (pin "L1") (pinfunction "GND_L1") (pintype "power_in"))
      (node (ref "U1") (pin "L11") (pinfunction "GND_L11") (pintype "power_in"))
      (node (ref "U1") (pin "M8") (pinfunction "GND_M8") (pintype "power_in"))
      (node (ref "U1") (pin "N15") (pinfunction "GND_N15") (pintype "power_in"))
      (node (ref "U1") (pin "N5") (pinfunction "GND_N5") (pintype "power_in"))
      (node (ref "U1") (pin "P12") (pinfunction "GND_P12") (pintype "power_in"))
      (node (ref "U1") (pin "P2") (pinfunction "GND_P2") (pintype "power_in"))
      (node (ref "U1") (pin "R9") (pinfunction "GND_R9") (pintype "power_in"))
      (node (ref "U1") (pin "T16") (pinfunction "GND_T16") (pintype "power_in"))
      (node (ref "U1") (pin "T6") (pinfunction "GND_T6") (pintype "power_in"))
      (node (ref "U6") (pin "4") (pinfunction "GND_4") (pintype "power_in"))
      (node (ref "U6") (pin "9") (pinfunction "EP_9") (pintype "passive"))
      (node (ref "U7") (pin "5") (pinfunction "GND_5") (pintype "input"))
      (node (ref "U7") (pin "9") (pinfunction "EPAD_9") (pintype "power_in"))
      (node (ref "X1") (pin "2") (pinfunction "GND_2") (pintype "power_in"))
    )
    (net (code "93") (name "Net-(D5-C)") (class "Default")
      (node (ref "D5") (pin "1") (pinfunction "C_1") (pintype "passive"))
      (node (ref "R8") (pin "1") (pinfunction "1_1") (pintype "passive"))
    )
    (net (code "94") (name "Net-(D6-A)") (class "Default")
      (node (ref "D6") (pin "2") (pinfunction "A_2") (pintype "passive"))
      (node (ref "R10") (pin "2") (pinfunction "2_2") (pintype "passive"))
    )
    (net (code "95") (name "Net-(X1-OE)") (class "Default")
      (node (ref "R5") (pin "1") (pinfunction "1_1") (pintype "passive"))
      (node (ref "X1") (pin "1") (pinfunction "OE_1") (pintype "input"))
    )
    (net (code "96") (name "VCCADC") (class "Default")
      (node (ref "C1") (pin "1") (pinfunction "1_1") (pintype "passive"))
      (node (ref "C18") (pin "2") (pinfunction "2_2") (pintype "passive"))
      (node (ref "FB1") (pin "1") (pinfunction "1_1") (pintype "passive"))
      (node (ref "U1") (pin "G8") (pinfunction "VCCADC_0_G8") (pintype "power_in"))
    )
    (net (code "97") (name "unconnected-(U1A-IO_0_14-PadK12)") (class "Default")
      (node (ref "U1") (pin "K12") (pinfunction "IO_0_14_K12") (pintype "bidirectional"))
    )
    (net (code "98") (name "unconnected-(U1A-IO_L3N_T0_DQS_EMCCLK_14-PadM15)") (class "Default")
      (node (ref "U1") (pin "M15") (pinfunction "IO_L3N_T0_DQS_EMCCLK_14_M15") (pintype "bidirectional+no_connect"))
    )
    (net (code "99") (name "unconnected-(U1A-IO_L4P_T0_D04_14-PadL14)") (class "Default")
      (node (ref "U1") (pin "L14") (pinfunction "IO_L4P_T0_D04_14_L14") (pintype "bidirectional"))
    )
    (net (code "100") (name "unconnected-(U1A-IO_L5N_T0_D07_14-PadL13)") (class "Default")
      (node (ref "U1") (pin "L13") (pinfunction "IO_L5N_T0_D07_14_L13") (pintype "bidirectional"))
    )
    (net (code "101") (name "unconnected-(U1A-IO_L5P_T0_D06_14-PadK13)") (class "Default")
      (node (ref "U1") (pin "K13") (pinfunction "IO_L5P_T0_D06_14_K13") (pintype "bidirectional"))
    )
    (net (code "102") (name "unconnected-(U1A-IO_L6N_T0_D08_VREF_14-PadM12)") (class "Default")
      (node (ref "U1") (pin "M12") (pinfunction "IO_L6N_T0_D08_VREF_14_M12") (pintype "bidirectional"))
    )
    (net (code "103") (name "unconnected-(U1A-IO_L7P_T1_D09_14-PadM16)") (class "Default")
      (node (ref "U1") (pin "M16") (pinfunction "IO_L7P_T1_D09_14_M16") (pintype "bidirectional"))
    )
    (net (code "104") (name "unconnected-(U1A-IO_L8N_T1_D12_14-PadP16)") (class "Default")
      (node (ref "U1") (pin "P16") (pinfunction "IO_L8N_T1_D12_14_P16") (pintype "bidirectional"))
    )
    (net (code "105") (name "unconnected-(U1A-IO_L8P_T1_D11_14-PadP15)") (class "Default")
      (node (ref "U1") (pin "P15") (pinfunction "IO_L8P_T1_D11_14_P15") (pintype "bidirectional"))
    )
    (net (code "106") (name "unconnected-(U1A-IO_L10P_T1_D14_14-PadT14)") (class "Default")
      (node (ref "U1") (pin "T14") (pinfunction "IO_L10P_T1_D14_14_T14") (pintype "bidirectional"))
    )
    (net (code "107") (name "unconnected-(U1A-IO_L11N_T1_SRCC_14-PadP13)") (class "Default")
      (node (ref "U1") (pin "P13") (pinfunction "IO_L11N_T1_SRCC_14_P13") (pintype "bidirectional"))
    )
    (net (code "108") (name "unconnected-(U1A-IO_L11P_T1_SRCC_14-PadN13)") (class "Default")
      (node (ref "U1") (pin "N13") (pinfunction "IO_L11P_T1_SRCC_14_N13") (pintype "bidirectional"))
    )
    (net (code "109") (name "unconnected-(U1A-IO_L13N_T2_MRCC_14-PadN12)") (class "Default")
      (node (ref "U1") (pin "N12") (pinfunction "IO_L13N_T2_MRCC_14_N12") (pintype "bidirectional"))
    )
    (net (code "110") (name "unconnected-(U1A-IO_L13P_T2_MRCC_14-PadN11)") (class "Default")
      (node (ref "U1") (pin "N11") (pinfunction "IO_L13P_T2_MRCC_14_N11") (pintype "bidirectional"))
    )
    (net (code "111") (name "unconnected-(U1A-IO_L14P_T2_SRCC_14-PadP10)") (class "Default")
      (node (ref "U1") (pin "P10") (pinfunction "IO_L14P_T2_SRCC_14_P10") (pintype "bidirectional"))
    )
    (net (code "112") (name "unconnected-(U1A-IO_L15N_T2_DQS_DOUT_CSO_B_14-PadT12)") (class "Default")
      (node (ref "U1") (pin "T12") (pinfunction "IO_L15N_T2_DQS_DOUT_CSO_B_14_T12") (pintype "bidirectional"))
    )
    (net (code "113") (name "unconnected-(U1A-IO_L15P_T2_DQS_RDWR_B_14-PadR12)") (class "Default")
      (node (ref "U1") (pin "R12") (pinfunction "IO_L15P_T2_DQS_RDWR_B_14_R12") (pintype "bidirectional"))
    )
    (net (code "114") (name "unconnected-(U1A-IO_L16N_T2_A15_D31_14-PadT13)") (class "Default")
      (node (ref "U1") (pin "T13") (pinfunction "IO_L16N_T2_A15_D31_14_T13") (pintype "bidirectional"))
    )
    (net (code "115") (name "unconnected-(U1A-IO_L18N_T2_A11_D27_14-PadP9)") (class "Default")
      (node (ref "U1") (pin "P9") (pinfunction "IO_L18N_T2_A11_D27_14_P9") (pintype "bidirectional"))
    )
    (net (code "116") (name "unconnected-(U1A-IO_L18P_T2_A12_D28_14-PadN9)") (class "Default")
      (node (ref "U1") (pin "N9") (pinfunction "IO_L18P_T2_A12_D28_14_N9") (pintype "bidirectional"))
    )
    (net (code "117") (name "unconnected-(U1A-IO_L19P_T3_A10_D26_14-PadM6)") (class "Default")
      (node (ref "U1") (pin "M6") (pinfunction "IO_L19P_T3_A10_D26_14_M6") (pintype "bidirectional"))
    )
    (net (code "118") (name "unconnected-(U1A-IO_L20N_T3_A07_D23_14-PadR8)") (class "Default")
      (node (ref "U1") (pin "R8") (pinfunction "IO_L20N_T3_A07_D23_14_R8") (pintype "bidirectional"))
    )
    (net (code "119") (name "unconnected-(U1A-IO_L20P_T3_A08_D24_14-PadP8)") (class "Default")
      (node (ref "U1") (pin "P8") (pinfunction "IO_L20P_T3_A08_D24_14_P8") (pintype "bidirectional"))
    )
    (net (code "120") (name "unconnected-(U1A-IO_L23N_T3_A02_D18_14-PadT5)") (class "Default")
      (node (ref "U1") (pin "T5") (pinfunction "IO_L23N_T3_A02_D18_14_T5") (pintype "bidirectional"))
    )
    (net (code "121") (name "unconnected-(U1A-IO_L24N_T3_A00_D16_14-PadR7)") (class "Default")
      (node (ref "U1") (pin "R7") (pinfunction "IO_L24N_T3_A00_D16_14_R7") (pintype "bidirectional"))
    )
    (net (code "122") (name "unconnected-(U1B-IO_0_15-PadD10)") (class "Default")
      (node (ref "U1") (pin "D10") (pinfunction "IO_0_15_D10") (pintype "bidirectional"))
    )
    (net (code "123") (name "unconnected-(U1B-IO_25_15-PadG11)") (class "Default")
      (node (ref "U1") (pin "G11") (pinfunction "IO_25_15_G11") (pintype "bidirectional"))
    )
    (net (code "124") (name "unconnected-(U1B-IO_L1N_T0_AD0N_15-PadC9)") (class "Default")
      (node (ref "U1") (pin "C9") (pinfunction "IO_L1N_T0_AD0N_15_C9") (pintype "bidirectional"))
    )
    (net (code "125") (name "unconnected-(U1B-IO_L1P_T0_AD0P_15-PadC8)") (class "Default")
      (node (ref "U1") (pin "C8") (pinfunction "IO_L1P_T0_AD0P_15_C8") (pintype "bidirectional"))
    )
    (net (code "126") (name "unconnected-(U1B-IO_L2N_T0_AD8N_15-PadA9)") (class "Default")
      (node (ref "U1") (pin "A9") (pinfunction "IO_L2N_T0_AD8N_15_A9") (pintype "bidirectional"))
    )
    (net (code "127") (name "unconnected-(U1B-IO_L2P_T0_AD8P_15-PadA8)") (class "Default")
      (node (ref "U1") (pin "A8") (pinfunction "IO_L2P_T0_AD8P_15_A8") (pintype "bidirectional"))
    )
    (net (code "128") (name "unconnected-(U1B-IO_L3P_T0_DQS_AD1P_15-PadB9)") (class "Default")
      (node (ref "U1") (pin "B9") (pinfunction "IO_L3P_T0_DQS_AD1P_15_B9") (pintype "bidirectional"))
    )
    (net (code "129") (name "unconnected-(U1B-IO_L4N_T0_15-PadB11)") (class "Default")
      (node (ref "U1") (pin "B11") (pinfunction "IO_L4N_T0_15_B11") (pintype "bidirectional"))
    )
    (net (code "130") (name "unconnected-(U1B-IO_L4P_T0_15-PadB10)") (class "Default")
      (node (ref "U1") (pin "B10") (pinfunction "IO_L4P_T0_15_B10") (pintype "bidirectional"))
    )
    (net (code "131") (name "unconnected-(U1B-IO_L5P_T0_AD9P_15-PadB12)") (class "Default")
      (node (ref "U1") (pin "B12") (pinfunction "IO_L5P_T0_AD9P_15_B12") (pintype "bidirectional"))
    )
    (net (code "132") (name "unconnected-(U1B-IO_L6N_T0_VREF_15-PadD9)") (class "Default")
      (node (ref "U1") (pin "D9") (pinfunction "IO_L6N_T0_VREF_15_D9") (pintype "bidirectional"))
    )
    (net (code "133") (name "unconnected-(U1B-IO_L6P_T0_15-PadD8)") (class "Default")
      (node (ref "U1") (pin "D8") (pinfunction "IO_L6P_T0_15_D8") (pintype "bidirectional"))
    )
    (net (code "134") (name "unconnected-(U1B-IO_L7N_T1_AD2N_15-PadA14)") (class "Default")
      (node (ref "U1") (pin "A14") (pinfunction "IO_L7N_T1_AD2N_15_A14") (pintype "bidirectional"))
    )
    (net (code "135") (name "unconnected-(U1B-IO_L8P_T1_AD10P_15-PadC14)") (class "Default")
      (node (ref "U1") (pin "C14") (pinfunction "IO_L8P_T1_AD10P_15_C14") (pintype "bidirectional"))
    )
    (net (code "136") (name "unconnected-(U1B-IO_L11N_T1_SRCC_15-PadC12)") (class "Default")
      (node (ref "U1") (pin "C12") (pinfunction "IO_L11N_T1_SRCC_15_C12") (pintype "bidirectional"))
    )
    (net (code "137") (name "unconnected-(U1B-IO_L11P_T1_SRCC_15-PadC11)") (class "Default")
      (node (ref "U1") (pin "C11") (pinfunction "IO_L11P_T1_SRCC_15_C11") (pintype "bidirectional"))
    )
    (net (code "138") (name "unconnected-(U1B-IO_L13N_T2_MRCC_15-PadE13)") (class "Default")
      (node (ref "U1") (pin "E13") (pinfunction "IO_L13N_T2_MRCC_15_E13") (pintype "bidirectional"))
    )
    (net (code "139") (name "unconnected-(U1B-IO_L13P_T2_MRCC_15-PadE12)") (class "Default")
      (node (ref "U1") (pin "E12") (pinfunction "IO_L13P_T2_MRCC_15_E12") (pintype "bidirectional"))
    )
    (net (code "140") (name "unconnected-(U1B-IO_L14N_T2_SRCC_15-PadD11)") (class "Default")
      (node (ref "U1") (pin "D11") (pinfunction "IO_L14N_T2_SRCC_15_D11") (pintype "bidirectional"))
    )
    (net (code "141") (name "unconnected-(U1B-IO_L14P_T2_SRCC_15-PadE11)") (class "Default")
      (node (ref "U1") (pin "E11") (pinfunction "IO_L14P_T2_SRCC_15_E11") (pintype "bidirectional"))
    )
    (net (code "142") (name "unconnected-(U1B-IO_L16N_T2_A27_15-PadF13)") (class "Default")
      (node (ref "U1") (pin "F13") (pinfunction "IO_L16N_T2_A27_15_F13") (pintype "bidirectional"))
    )
    (net (code "143") (name "unconnected-(U1B-IO_L16P_T2_A28_15-PadF12)") (class "Default")
      (node (ref "U1") (pin "F12") (pinfunction "IO_L16P_T2_A28_15_F12") (pintype "bidirectional"))
    )
    (net (code "144") (name "unconnected-(U1B-IO_L19N_T3_A21_VREF_15-PadG12)") (class "Default")
      (node (ref "U1") (pin "G12") (pinfunction "IO_L19N_T3_A21_VREF_15_G12") (pintype "bidirectional"))
    )
    (net (code "145") (name "unconnected-(U1B-IO_L19P_T3_A22_15-PadH11)") (class "Default")
      (node (ref "U1") (pin "H11") (pinfunction "IO_L19P_T3_A22_15_H11") (pintype "bidirectional"))
    )
    (net (code "146") (name "unconnected-(U1B-IO_L20N_T3_A19_15-PadH13)") (class "Default")
      (node (ref "U1") (pin "H13") (pinfunction "IO_L20N_T3_A19_15_H13") (pintype "bidirectional"))
    )
    (net (code "147") (name "unconnected-(U1B-IO_L20P_T3_A20_15-PadH12)") (class "Default")
      (node (ref "U1") (pin "H12") (pinfunction "IO_L20P_T3_A20_15_H12") (pintype "bidirectional"))
    )
    (net (code "148") (name "unconnected-(U1B-IO_L21N_T3_DQS_A18_15-PadF14)") (class "Default")
      (node (ref "U1") (pin "F14") (pinfunction "IO_L21N_T3_DQS_A18_15_F14") (pintype "bidirectional"))
    )
    (net (code "149") (name "unconnected-(U1B-IO_L21P_T3_DQS_15-PadG14)") (class "Default")
      (node (ref "U1") (pin "G14") (pinfunction "IO_L21P_T3_DQS_15_G14") (pintype "bidirectional"))
    )
    (net (code "150") (name "unconnected-(U1C-IO_0_34-PadL5)") (class "Default")
      (node (ref "U1") (pin "L5") (pinfunction "IO_0_34_L5") (pintype "bidirectional"))
    )
    (net (code "151") (name "unconnected-(U1C-IO_L1N_T0_34-PadM4)") (class "Default")
      (node (ref "U1") (pin "M4") (pinfunction "IO_L1N_T0_34_M4") (pintype "bidirectional"))
    )
    (net (code "152") (name "unconnected-(U1C-IO_L1P_T0_34-PadL4)") (class "Default")
      (node (ref "U1") (pin "L4") (pinfunction "IO_L1P_T0_34_L4") (pintype "bidirectional"))
    )
    (net (code "153") (name "unconnected-(U1C-IO_L3P_T0_DQS_34-PadN3)") (class "Default")
      (node (ref "U1") (pin "N3") (pinfunction "IO_L3P_T0_DQS_34_N3") (pintype "bidirectional"))
    )
    (net (code "154") (name "unconnected-(U1C-IO_L4N_T0_34-PadP1)") (class "Default")
      (node (ref "U1") (pin "P1") (pinfunction "IO_L4N_T0_34_P1") (pintype "bidirectional"))
    )
    (net (code "155") (name "unconnected-(U1C-IO_L5N_T0_34-PadP3)") (class "Default")
      (node (ref "U1") (pin "P3") (pinfunction "IO_L5N_T0_34_P3") (pintype "bidirectional"))
    )
    (net (code "156") (name "unconnected-(U1C-IO_L5P_T0_34-PadP4)") (class "Default")
      (node (ref "U1") (pin "P4") (pinfunction "IO_L5P_T0_34_P4") (pintype "bidirectional"))
    )
    (net (code "157") (name "unconnected-(U1C-IO_L6P_T0_34-PadM5)") (class "Default")
      (node (ref "U1") (pin "M5") (pinfunction "IO_L6P_T0_34_M5") (pintype "bidirectional"))
    )
    (net (code "158") (name "unconnected-(U1C-IO_L8N_T1_34-PadT2)") (class "Default")
      (node (ref "U1") (pin "T2") (pinfunction "IO_L8N_T1_34_T2") (pintype "bidirectional"))
    )
    (net (code "159") (name "unconnected-(U1C-IO_L8P_T1_34-PadR3)") (class "Default")
      (node (ref "U1") (pin "R3") (pinfunction "IO_L8P_T1_34_R3") (pintype "bidirectional"))
    )
    (net (code "160") (name "unconnected-(U1C-IO_L9N_T1_DQS_34-PadT3)") (class "Default")
      (node (ref "U1") (pin "T3") (pinfunction "IO_L9N_T1_DQS_34_T3") (pintype "bidirectional"))
    )
    (net (code "161") (name "unconnected-(U1C-IO_L9P_T1_DQS_34-PadT4)") (class "Default")
      (node (ref "U1") (pin "T4") (pinfunction "IO_L9P_T1_DQS_34_T4") (pintype "bidirectional"))
    )
    (net (code "162") (name "unconnected-(U1C-IO_L10P_T1_34-PadP5)") (class "Default")
      (node (ref "U1") (pin "P5") (pinfunction "IO_L10P_T1_34_P5") (pintype "bidirectional"))
    )
    (net (code "163") (name "unconnected-(U1D-IO_0_35-PadE6)") (class "Default")
      (node (ref "U1") (pin "E6") (pinfunction "IO_0_35_E6") (pintype "bidirectional"))
    )
    (net (code "164") (name "unconnected-(U1D-IO_25_35-PadK5)") (class "Default")
      (node (ref "U1") (pin "K5") (pinfunction "IO_25_35_K5") (pintype "bidirectional"))
    )
    (net (code "165") (name "unconnected-(U1D-IO_L1N_T0_AD4N_35-PadA7)") (class "Default")
      (node (ref "U1") (pin "A7") (pinfunction "IO_L1N_T0_AD4N_35_A7") (pintype "bidirectional"))
    )
    (net (code "166") (name "unconnected-(U1D-IO_L1P_T0_AD4P_35-PadB7)") (class "Default")
      (node (ref "U1") (pin "B7") (pinfunction "IO_L1P_T0_AD4P_35_B7") (pintype "bidirectional"))
    )
    (net (code "167") (name "unconnected-(U1D-IO_L2N_T0_AD12N_35-PadB5)") (class "Default")
      (node (ref "U1") (pin "B5") (pinfunction "IO_L2N_T0_AD12N_35_B5") (pintype "bidirectional"))
    )
    (net (code "168") (name "unconnected-(U1D-IO_L2P_T0_AD12P_35-PadB6)") (class "Default")
      (node (ref "U1") (pin "B6") (pinfunction "IO_L2P_T0_AD12P_35_B6") (pintype "bidirectional"))
    )
    (net (code "169") (name "unconnected-(U1D-IO_L3N_T0_DQS_AD5N_35-PadA4)") (class "Default")
      (node (ref "U1") (pin "A4") (pinfunction "IO_L3N_T0_DQS_AD5N_35_A4") (pintype "bidirectional"))
    )
    (net (code "170") (name "unconnected-(U1D-IO_L3P_T0_DQS_AD5P_35-PadA5)") (class "Default")
      (node (ref "U1") (pin "A5") (pinfunction "IO_L3P_T0_DQS_AD5P_35_A5") (pintype "bidirectional"))
    )
    (net (code "171") (name "unconnected-(U1D-IO_L4N_T0_35-PadA3)") (class "Default")
      (node (ref "U1") (pin "A3") (pinfunction "IO_L4N_T0_35_A3") (pintype "bidirectional"))
    )
    (net (code "172") (name "unconnected-(U1D-IO_L4P_T0_35-PadB4)") (class "Default")
      (node (ref "U1") (pin "B4") (pinfunction "IO_L4P_T0_35_B4") (pintype "bidirectional"))
    )
    (net (code "173") (name "unconnected-(U1D-IO_L8N_T1_AD14N_35-PadA2)") (class "Default")
      (node (ref "U1") (pin "A2") (pinfunction "IO_L8N_T1_AD14N_35_A2") (pintype "bidirectional"))
    )
    (net (code "174") (name "unconnected-(U1D-IO_L8P_T1_AD14P_35-PadB2)") (class "Default")
      (node (ref "U1") (pin "B2") (pinfunction "IO_L8P_T1_AD14P_35_B2") (pintype "bidirectional"))
    )
    (net (code "175") (name "unconnected-(U1D-IO_L9N_T1_DQS_AD7N_35-PadB1)") (class "Default")
      (node (ref "U1") (pin "B1") (pinfunction "IO_L9N_T1_DQS_AD7N_35_B1") (pintype "bidirectional"))
    )
    (net (code "176") (name "unconnected-(U1D-IO_L9P_T1_DQS_AD7P_35-PadC1)") (class "Default")
      (node (ref "U1") (pin "C1") (pinfunction "IO_L9P_T1_DQS_AD7P_35_C1") (pintype "bidirectional"))
    )
    (net (code "177") (name "unconnected-(U1D-IO_L10N_T1_AD15N_35-PadD1)") (class "Default")
      (node (ref "U1") (pin "D1") (pinfunction "IO_L10N_T1_AD15N_35_D1") (pintype "bidirectional"))
    )
    (net (code "178") (name "unconnected-(U1D-IO_L10P_T1_AD15P_35-PadE2)") (class "Default")
      (node (ref "U1") (pin "E2") (pinfunction "IO_L10P_T1_AD15P_35_E2") (pintype "bidirectional"))
    )
    (net (code "179") (name "unconnected-(U1D-IO_L11P_T1_SRCC_35-PadE3)") (class "Default")
      (node (ref "U1") (pin "E3") (pinfunction "IO_L11P_T1_SRCC_35_E3") (pintype "bidirectional"))
    )
    (net (code "180") (name "unconnected-(U1D-IO_L14N_T2_SRCC_35-PadF3)") (class "Default")
      (node (ref "U1") (pin "F3") (pinfunction "IO_L14N_T2_SRCC_35_F3") (pintype "bidirectional"))
    )
    (net (code "181") (name "unconnected-(U1D-IO_L14P_T2_SRCC_35-PadF4)") (class "Default")
      (node (ref "U1") (pin "F4") (pinfunction "IO_L14P_T2_SRCC_35_F4") (pintype "bidirectional"))
    )
    (net (code "182") (name "unconnected-(U1D-IO_L15N_T2_DQS_35-PadE1)") (class "Default")
      (node (ref "U1") (pin "E1") (pinfunction "IO_L15N_T2_DQS_35_E1") (pintype "bidirectional"))
    )
    (net (code "183") (name "unconnected-(U1D-IO_L15P_T2_DQS_35-PadF2)") (class "Default")
      (node (ref "U1") (pin "F2") (pinfunction "IO_L15P_T2_DQS_35_F2") (pintype "bidirectional"))
    )
    (net (code "184") (name "unconnected-(U1D-IO_L17N_T2_35-PadG1)") (class "Default")
      (node (ref "U1") (pin "G1") (pinfunction "IO_L17N_T2_35_G1") (pintype "bidirectional"))
    )
    (net (code "185") (name "unconnected-(U1D-IO_L17P_T2_35-PadG2)") (class "Default")
      (node (ref "U1") (pin "G2") (pinfunction "IO_L17P_T2_35_G2") (pintype "bidirectional"))
    )
    (net (code "186") (name "unconnected-(U1D-IO_L18N_T2_35-PadH4)") (class "Default")
      (node (ref "U1") (pin "H4") (pinfunction "IO_L18N_T2_35_H4") (pintype "bidirectional"))
    )
    (net (code "187") (name "unconnected-(U1D-IO_L18P_T2_35-PadH5)") (class "Default")
      (node (ref "U1") (pin "H5") (pinfunction "IO_L18P_T2_35_H5") (pintype "bidirectional"))
    )
    (net (code "188") (name "unconnected-(U1D-IO_L19N_T3_VREF_35-PadJ4)") (class "Default")
      (node (ref "U1") (pin "J4") (pinfunction "IO_L19N_T3_VREF_35_J4") (pintype "bidirectional"))
    )
    (net (code "189") (name "unconnected-(U1D-IO_L19P_T3_35-PadJ5)") (class "Default")
      (node (ref "U1") (pin "J5") (pinfunction "IO_L19P_T3_35_J5") (pintype "bidirectional"))
    )
    (net (code "190") (name "unconnected-(U1D-IO_L20N_T3_35-PadH1)") (class "Default")
      (node (ref "U1") (pin "H1") (pinfunction "IO_L20N_T3_35_H1") (pintype "bidirectional"))
    )
    (net (code "191") (name "unconnected-(U1D-IO_L20P_T3_35-PadH2)") (class "Default")
      (node (ref "U1") (pin "H2") (pinfunction "IO_L20P_T3_35_H2") (pintype "bidirectional"))
    )
    (net (code "192") (name "unconnected-(U1D-IO_L21N_T3_DQS_35-PadH3)") (class "Default")
      (node (ref "U1") (pin "H3") (pinfunction "IO_L21N_T3_DQS_35_H3") (pintype "bidirectional"))
    )
    (net (code "193") (name "unconnected-(U1D-IO_L21P_T3_DQS_35-PadJ3)") (class "Default")
      (node (ref "U1") (pin "J3") (pinfunction "IO_L21P_T3_DQS_35_J3") (pintype "bidirectional"))
    )
    (net (code "194") (name "unconnected-(U1D-IO_L22N_T3_35-PadJ1)") (class "Default")
      (node (ref "U1") (pin "J1") (pinfunction "IO_L22N_T3_35_J1") (pintype "bidirectional"))
    )
    (net (code "195") (name "unconnected-(U1D-IO_L22P_T3_35-PadK1)") (class "Default")
      (node (ref "U1") (pin "K1") (pinfunction "IO_L22P_T3_35_K1") (pintype "bidirectional"))
    )
    (net (code "196") (name "unconnected-(U1D-IO_L23N_T3_35-PadL2)") (class "Default")
      (node (ref "U1") (pin "L2") (pinfunction "IO_L23N_T3_35_L2") (pintype "bidirectional"))
    )
    (net (code "197") (name "unconnected-(U1D-IO_L23P_T3_35-PadL3)") (class "Default")
      (node (ref "U1") (pin "L3") (pinfunction "IO_L23P_T3_35_L3") (pintype "bidirectional"))
    )
    (net (code "198") (name "unconnected-(U1D-IO_L24N_T3_35-PadK2)") (class "Default")
      (node (ref "U1") (pin "K2") (pinfunction "IO_L24N_T3_35_K2") (pintype "bidirectional"))
    )
    (net (code "199") (name "unconnected-(U1D-IO_L24P_T3_35-PadK3)") (class "Default")
      (node (ref "U1") (pin "K3") (pinfunction "IO_L24P_T3_35_K3") (pintype "bidirectional"))
    )
    (net (code "200") (name "unconnected-(U7-NC-Pad7)") (class "Default")
      (node (ref "U7") (pin "7") (pinfunction "NC_7") (pintype "input+no_connect"))
    )
  )
)
